# HashUnit2.net
KiCad netlist of a schematic drawn in Altium Designer
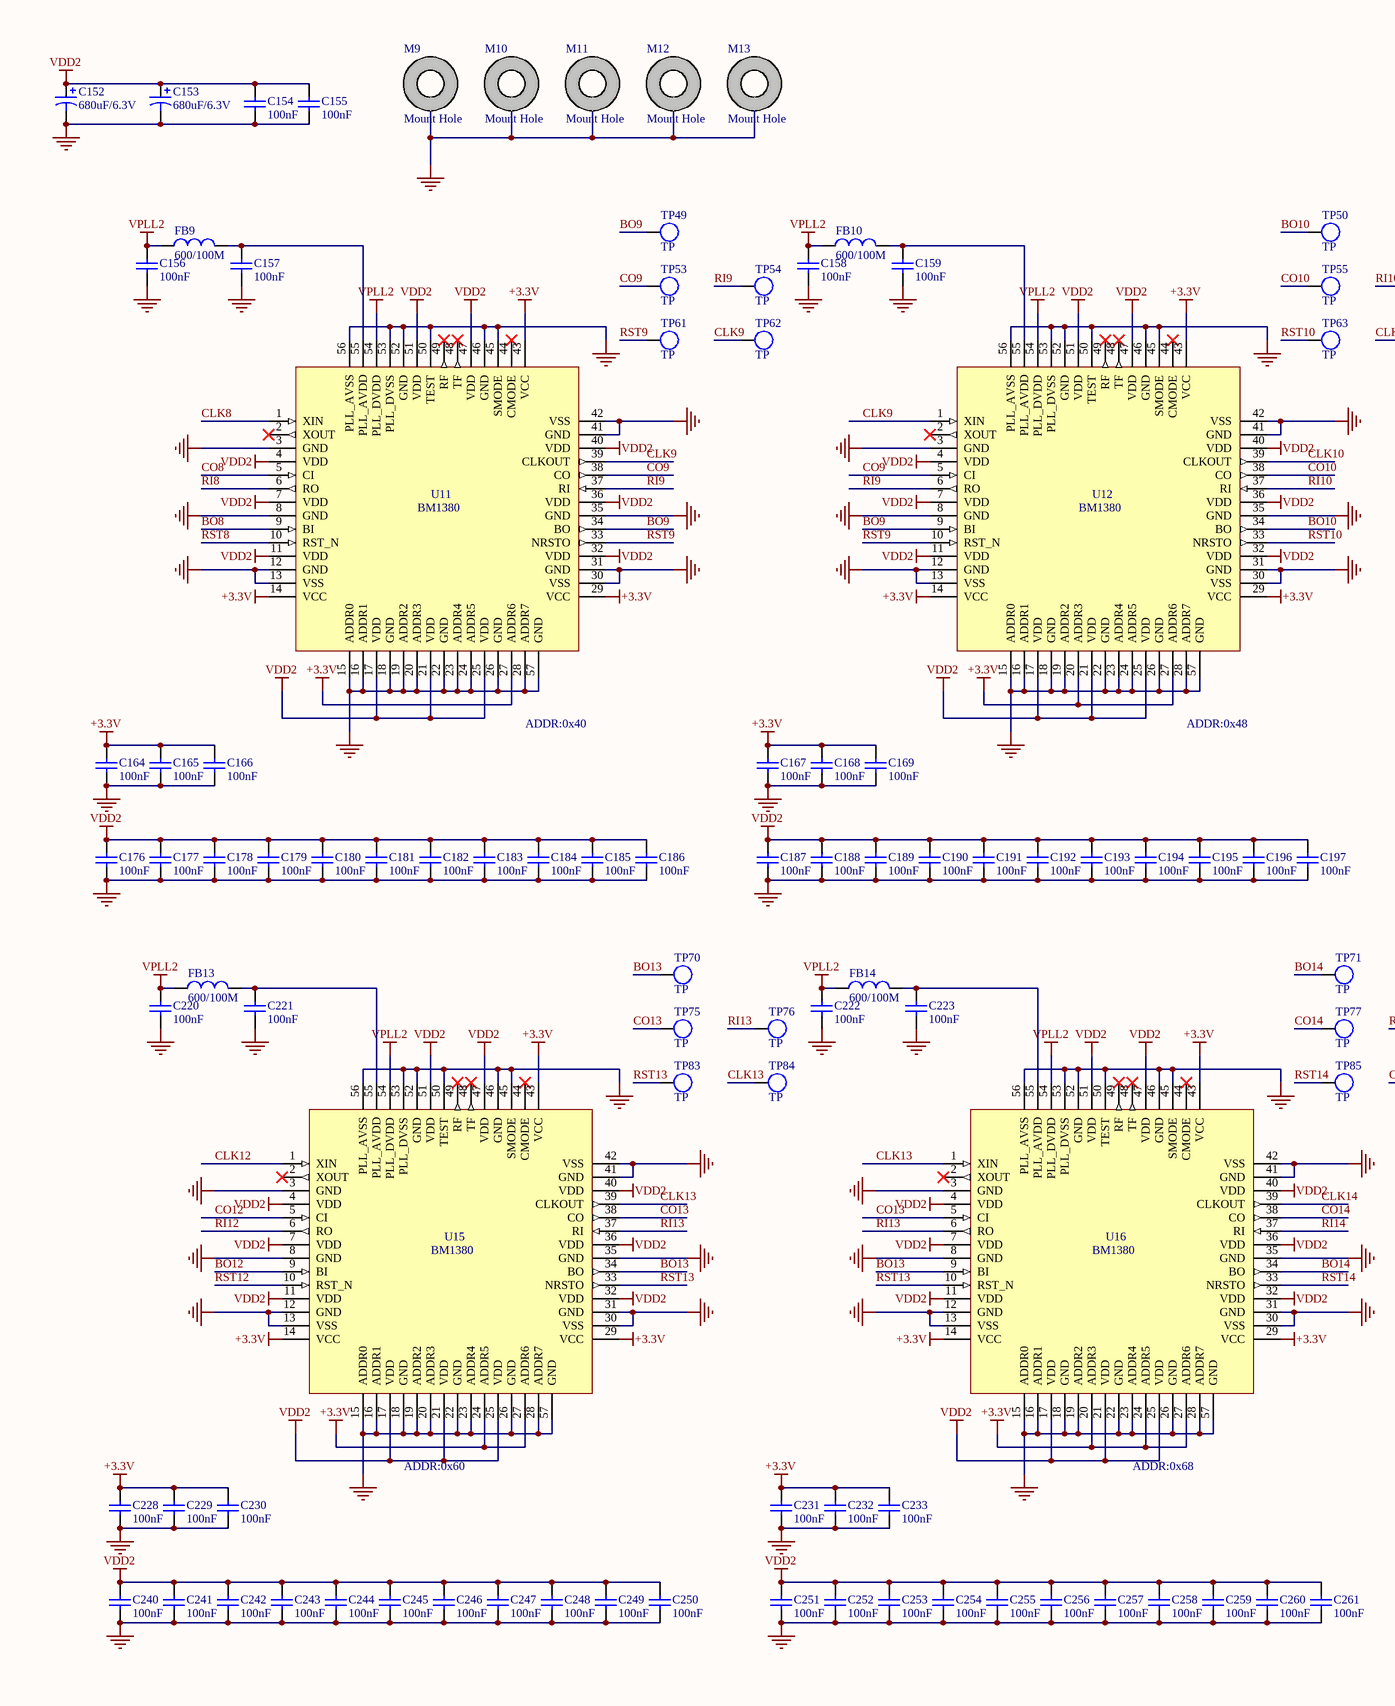
[diagram p0: HashUnit2.SchDoc, left]
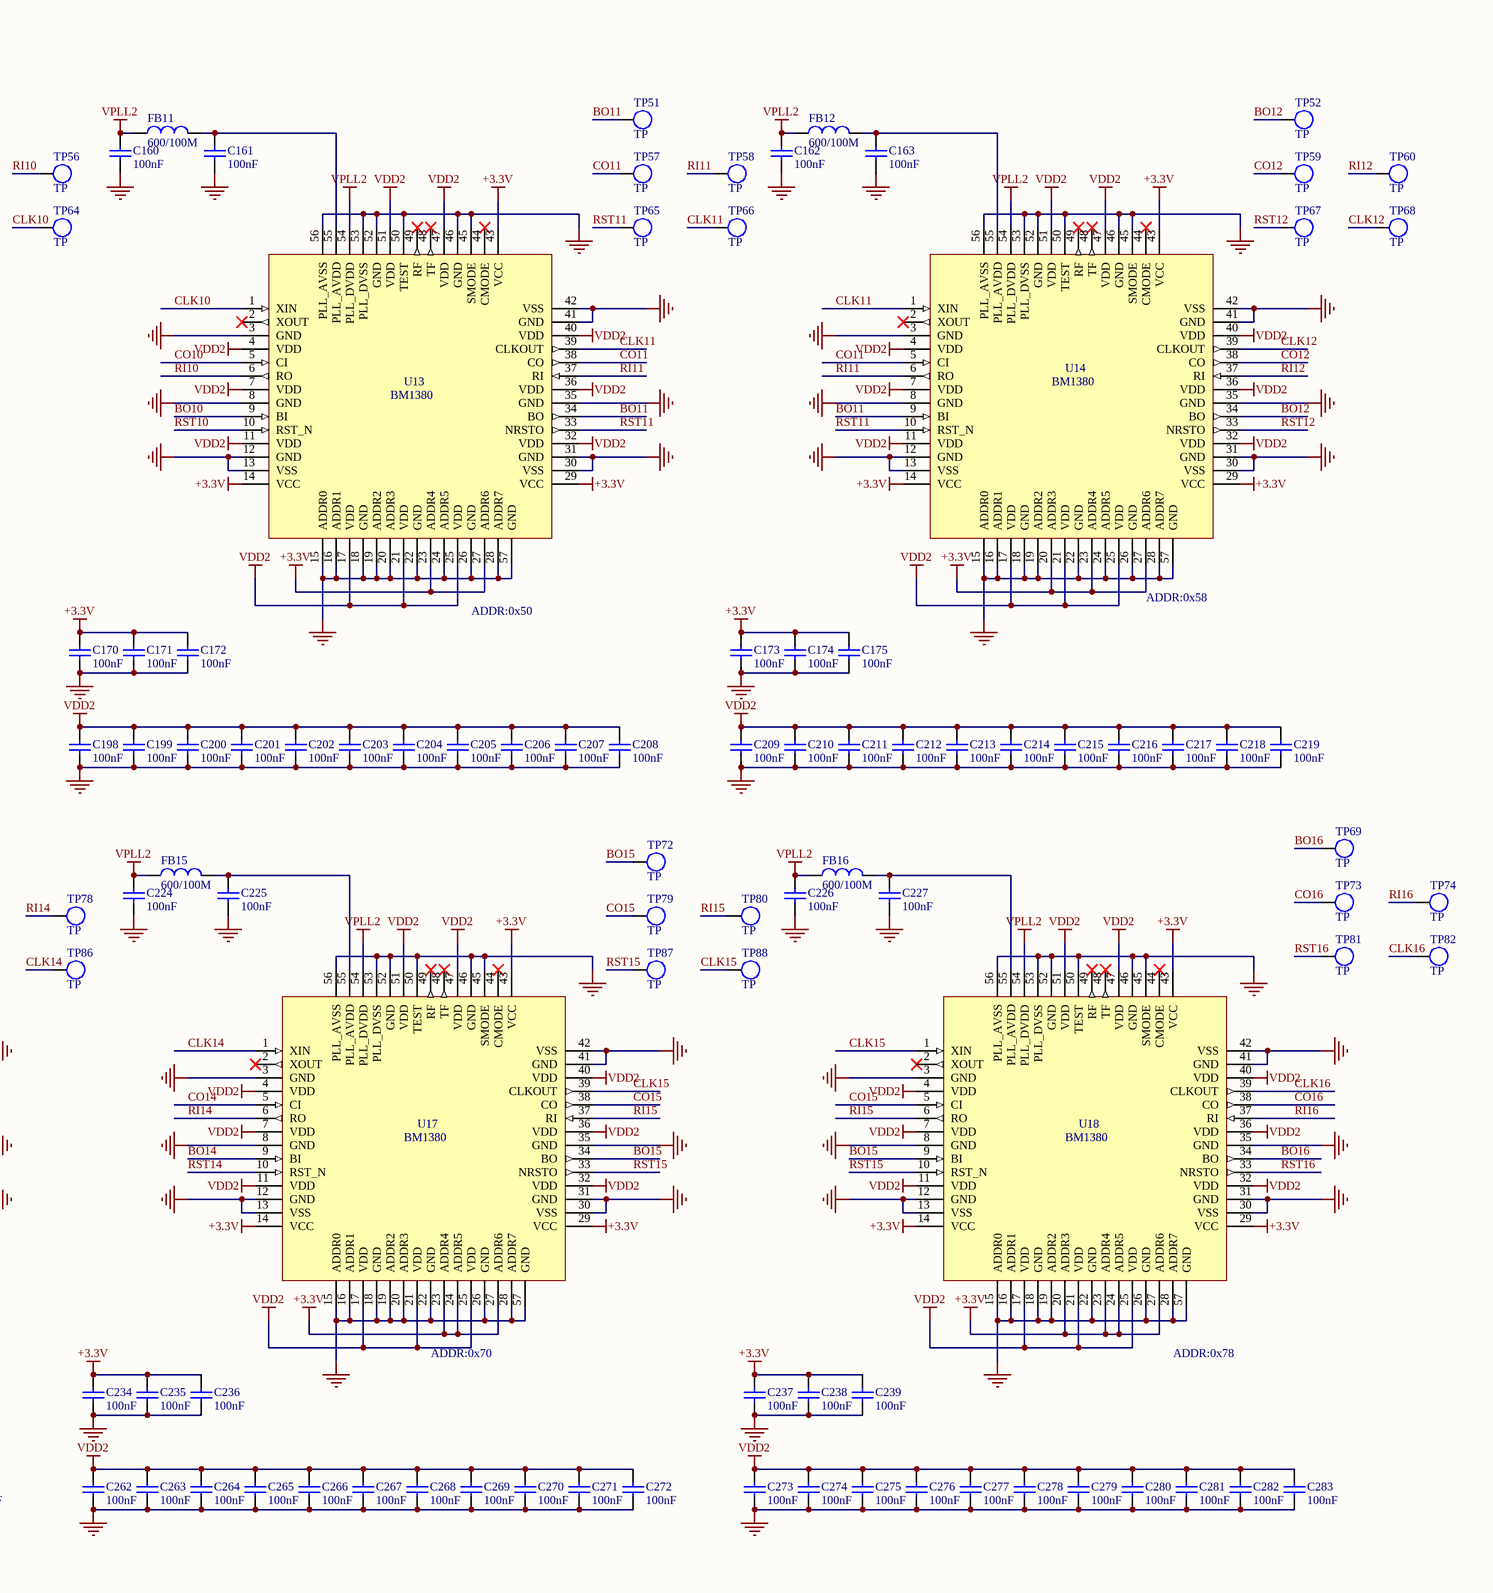
[diagram p1: HashUnit2.SchDoc, right]

(export (version "E")
  (design (tool "Eeschema 10.0.6"))
  (components
    (comp (ref "C152")
      (value "680uF/6.3V")
      (footprint "D")
      (description "Solid Tantalum Chip Capacitor, T492 Series - CWR11 Style Per Mil-PRF-55365/8")
      (fields (field (name "PUBLISHER") "Altium Limited"))
      (libsource (lib "KEMET Chip Capacitor") (part "T492C"))
    )
    (comp (ref "C153")
      (value "680uF/6.3V")
      (footprint "D")
      (description "Solid Tantalum Chip Capacitor, T492 Series - CWR11 Style Per Mil-PRF-55365/8")
      (fields (field (name "PUBLISHER") "Altium Limited"))
      (libsource (lib "KEMET Chip Capacitor") (part "T492C"))
    )
    (comp (ref "C154")
      (value "100nF")
      (footprint "CC0603(1608)")
      (description "Capacitor (Semiconductor SIM Model)")
      (fields (field (name "PUBLISHER") "Altium Limited"))
      (libsource (lib "Miscellaneous Devices") (part "Cap Semi"))
    )
    (comp (ref "C155")
      (value "100nF")
      (footprint "CC0603(1608)")
      (description "Capacitor (Semiconductor SIM Model)")
      (fields (field (name "PUBLISHER") "Altium Limited"))
      (libsource (lib "Miscellaneous Devices") (part "Cap Semi"))
    )
    (comp (ref "C156")
      (value "100nF")
      (footprint "CC0603(1608)")
      (description "Capacitor")
      (fields (field (name "PUBLISHER") "Altium Limited"))
      (libsource (lib "BitMain_Miner_1") (part "Cap"))
    )
    (comp (ref "C157")
      (value "100nF")
      (footprint "CC0603(1608)")
      (description "Capacitor")
      (fields (field (name "PUBLISHER") "Altium Limited"))
      (libsource (lib "BitMain_Miner_1") (part "Cap"))
    )
    (comp (ref "C158")
      (value "100nF")
      (footprint "CC0603(1608)")
      (description "Capacitor")
      (fields (field (name "PUBLISHER") "Altium Limited"))
      (libsource (lib "BitMain_Miner_1") (part "Cap"))
    )
    (comp (ref "C159")
      (value "100nF")
      (footprint "CC0603(1608)")
      (description "Capacitor")
      (fields (field (name "PUBLISHER") "Altium Limited"))
      (libsource (lib "BitMain_Miner_1") (part "Cap"))
    )
    (comp (ref "C160")
      (value "100nF")
      (footprint "CC0603(1608)")
      (description "Capacitor")
      (fields (field (name "PUBLISHER") "Altium Limited"))
      (libsource (lib "BitMain_Miner_1") (part "Cap"))
    )
    (comp (ref "C161")
      (value "100nF")
      (footprint "CC0603(1608)")
      (description "Capacitor")
      (fields (field (name "PUBLISHER") "Altium Limited"))
      (libsource (lib "BitMain_Miner_1") (part "Cap"))
    )
    (comp (ref "C162")
      (value "100nF")
      (footprint "CC0603(1608)")
      (description "Capacitor")
      (fields (field (name "PUBLISHER") "Altium Limited"))
      (libsource (lib "BitMain_Miner_1") (part "Cap"))
    )
    (comp (ref "C163")
      (value "100nF")
      (footprint "CC0603(1608)")
      (description "Capacitor")
      (fields (field (name "PUBLISHER") "Altium Limited"))
      (libsource (lib "BitMain_Miner_1") (part "Cap"))
    )
    (comp (ref "C164")
      (value "100nF")
      (footprint "CC0603(1608)")
      (description "Capacitor")
      (fields (field (name "PUBLISHER") "Altium Limited"))
      (libsource (lib "BitMain_Miner_1") (part "Cap"))
    )
    (comp (ref "C165")
      (value "100nF")
      (footprint "CC0603(1608)")
      (description "Capacitor")
      (fields (field (name "PUBLISHER") "Altium Limited"))
      (libsource (lib "BitMain_Miner_1") (part "Cap"))
    )
    (comp (ref "C166")
      (value "100nF")
      (footprint "CC0603(1608)")
      (description "Capacitor")
      (fields (field (name "PUBLISHER") "Altium Limited"))
      (libsource (lib "BitMain_Miner_1") (part "Cap"))
    )
    (comp (ref "C167")
      (value "100nF")
      (footprint "CC0603(1608)")
      (description "Capacitor")
      (fields (field (name "PUBLISHER") "Altium Limited"))
      (libsource (lib "BitMain_Miner_1") (part "Cap"))
    )
    (comp (ref "C168")
      (value "100nF")
      (footprint "CC0603(1608)")
      (description "Capacitor")
      (fields (field (name "PUBLISHER") "Altium Limited"))
      (libsource (lib "BitMain_Miner_1") (part "Cap"))
    )
    (comp (ref "C169")
      (value "100nF")
      (footprint "CC0603(1608)")
      (description "Capacitor")
      (fields (field (name "PUBLISHER") "Altium Limited"))
      (libsource (lib "BitMain_Miner_1") (part "Cap"))
    )
    (comp (ref "C170")
      (value "100nF")
      (footprint "CC0603(1608)")
      (description "Capacitor")
      (fields (field (name "PUBLISHER") "Altium Limited"))
      (libsource (lib "BitMain_Miner_1") (part "Cap"))
    )
    (comp (ref "C171")
      (value "100nF")
      (footprint "CC0603(1608)")
      (description "Capacitor")
      (fields (field (name "PUBLISHER") "Altium Limited"))
      (libsource (lib "BitMain_Miner_1") (part "Cap"))
    )
    (comp (ref "C172")
      (value "100nF")
      (footprint "CC0603(1608)")
      (description "Capacitor")
      (fields (field (name "PUBLISHER") "Altium Limited"))
      (libsource (lib "BitMain_Miner_1") (part "Cap"))
    )
    (comp (ref "C173")
      (value "100nF")
      (footprint "CC0603(1608)")
      (description "Capacitor")
      (fields (field (name "PUBLISHER") "Altium Limited"))
      (libsource (lib "BitMain_Miner_1") (part "Cap"))
    )
    (comp (ref "C174")
      (value "100nF")
      (footprint "CC0603(1608)")
      (description "Capacitor")
      (fields (field (name "PUBLISHER") "Altium Limited"))
      (libsource (lib "BitMain_Miner_1") (part "Cap"))
    )
    (comp (ref "C175")
      (value "100nF")
      (footprint "CC0603(1608)")
      (description "Capacitor")
      (fields (field (name "PUBLISHER") "Altium Limited"))
      (libsource (lib "BitMain_Miner_1") (part "Cap"))
    )
    (comp (ref "C176")
      (value "100nF")
      (footprint "CC0603(1608)")
      (description "Capacitor")
      (fields (field (name "PUBLISHER") "Altium Limited"))
      (libsource (lib "BitMain_Miner_1") (part "Cap"))
    )
    (comp (ref "C177")
      (value "100nF")
      (footprint "CC0603(1608)")
      (description "Capacitor")
      (fields (field (name "PUBLISHER") "Altium Limited"))
      (libsource (lib "BitMain_Miner_1") (part "Cap"))
    )
    (comp (ref "C178")
      (value "100nF")
      (footprint "CC0603(1608)")
      (description "Capacitor")
      (fields (field (name "PUBLISHER") "Altium Limited"))
      (libsource (lib "BitMain_Miner_1") (part "Cap"))
    )
    (comp (ref "C179")
      (value "100nF")
      (footprint "CC0603(1608)")
      (description "Capacitor")
      (fields (field (name "PUBLISHER") "Altium Limited"))
      (libsource (lib "BitMain_Miner_1") (part "Cap"))
    )
    (comp (ref "C180")
      (value "100nF")
      (footprint "CC0603(1608)")
      (description "Capacitor")
      (fields (field (name "PUBLISHER") "Altium Limited"))
      (libsource (lib "BitMain_Miner_1") (part "Cap"))
    )
    (comp (ref "C181")
      (value "100nF")
      (footprint "CC0603(1608)")
      (description "Capacitor")
      (fields (field (name "PUBLISHER") "Altium Limited"))
      (libsource (lib "BitMain_Miner_1") (part "Cap"))
    )
    (comp (ref "C182")
      (value "100nF")
      (footprint "CC0603(1608)")
      (description "Capacitor")
      (fields (field (name "PUBLISHER") "Altium Limited"))
      (libsource (lib "BitMain_Miner_1") (part "Cap"))
    )
    (comp (ref "C183")
      (value "100nF")
      (footprint "CC0603(1608)")
      (description "Capacitor")
      (fields (field (name "PUBLISHER") "Altium Limited"))
      (libsource (lib "BitMain_Miner_1") (part "Cap"))
    )
    (comp (ref "C184")
      (value "100nF")
      (footprint "CC0603(1608)")
      (description "Capacitor")
      (fields (field (name "PUBLISHER") "Altium Limited"))
      (libsource (lib "BitMain_Miner_1") (part "Cap"))
    )
    (comp (ref "C185")
      (value "100nF")
      (footprint "CC0603(1608)")
      (description "Capacitor")
      (fields (field (name "PUBLISHER") "Altium Limited"))
      (libsource (lib "BitMain_Miner_1") (part "Cap"))
    )
    (comp (ref "C186")
      (value "100nF")
      (footprint "CC0603(1608)")
      (description "Capacitor")
      (fields (field (name "PUBLISHER") "Altium Limited"))
      (libsource (lib "BitMain_Miner_1") (part "Cap"))
    )
    (comp (ref "C187")
      (value "100nF")
      (footprint "CC0603(1608)")
      (description "Capacitor")
      (fields (field (name "PUBLISHER") "Altium Limited"))
      (libsource (lib "BitMain_Miner_1") (part "Cap"))
    )
    (comp (ref "C188")
      (value "100nF")
      (footprint "CC0603(1608)")
      (description "Capacitor")
      (fields (field (name "PUBLISHER") "Altium Limited"))
      (libsource (lib "BitMain_Miner_1") (part "Cap"))
    )
    (comp (ref "C189")
      (value "100nF")
      (footprint "CC0603(1608)")
      (description "Capacitor")
      (fields (field (name "PUBLISHER") "Altium Limited"))
      (libsource (lib "BitMain_Miner_1") (part "Cap"))
    )
    (comp (ref "C190")
      (value "100nF")
      (footprint "CC0603(1608)")
      (description "Capacitor")
      (fields (field (name "PUBLISHER") "Altium Limited"))
      (libsource (lib "BitMain_Miner_1") (part "Cap"))
    )
    (comp (ref "C191")
      (value "100nF")
      (footprint "CC0603(1608)")
      (description "Capacitor")
      (fields (field (name "PUBLISHER") "Altium Limited"))
      (libsource (lib "BitMain_Miner_1") (part "Cap"))
    )
    (comp (ref "C192")
      (value "100nF")
      (footprint "CC0603(1608)")
      (description "Capacitor")
      (fields (field (name "PUBLISHER") "Altium Limited"))
      (libsource (lib "BitMain_Miner_1") (part "Cap"))
    )
    (comp (ref "C193")
      (value "100nF")
      (footprint "CC0603(1608)")
      (description "Capacitor")
      (fields (field (name "PUBLISHER") "Altium Limited"))
      (libsource (lib "BitMain_Miner_1") (part "Cap"))
    )
    (comp (ref "C194")
      (value "100nF")
      (footprint "CC0603(1608)")
      (description "Capacitor")
      (fields (field (name "PUBLISHER") "Altium Limited"))
      (libsource (lib "BitMain_Miner_1") (part "Cap"))
    )
    (comp (ref "C195")
      (value "100nF")
      (footprint "CC0603(1608)")
      (description "Capacitor")
      (fields (field (name "PUBLISHER") "Altium Limited"))
      (libsource (lib "BitMain_Miner_1") (part "Cap"))
    )
    (comp (ref "C196")
      (value "100nF")
      (footprint "CC0603(1608)")
      (description "Capacitor")
      (fields (field (name "PUBLISHER") "Altium Limited"))
      (libsource (lib "BitMain_Miner_1") (part "Cap"))
    )
    (comp (ref "C197")
      (value "100nF")
      (footprint "CC0603(1608)")
      (description "Capacitor")
      (fields (field (name "PUBLISHER") "Altium Limited"))
      (libsource (lib "BitMain_Miner_1") (part "Cap"))
    )
    (comp (ref "C198")
      (value "100nF")
      (footprint "CC0603(1608)")
      (description "Capacitor")
      (fields (field (name "PUBLISHER") "Altium Limited"))
      (libsource (lib "BitMain_Miner_1") (part "Cap"))
    )
    (comp (ref "C199")
      (value "100nF")
      (footprint "CC0603(1608)")
      (description "Capacitor")
      (fields (field (name "PUBLISHER") "Altium Limited"))
      (libsource (lib "BitMain_Miner_1") (part "Cap"))
    )
    (comp (ref "C200")
      (value "100nF")
      (footprint "CC0603(1608)")
      (description "Capacitor")
      (fields (field (name "PUBLISHER") "Altium Limited"))
      (libsource (lib "BitMain_Miner_1") (part "Cap"))
    )
    (comp (ref "C201")
      (value "100nF")
      (footprint "CC0603(1608)")
      (description "Capacitor")
      (fields (field (name "PUBLISHER") "Altium Limited"))
      (libsource (lib "BitMain_Miner_1") (part "Cap"))
    )
    (comp (ref "C202")
      (value "100nF")
      (footprint "CC0603(1608)")
      (description "Capacitor")
      (fields (field (name "PUBLISHER") "Altium Limited"))
      (libsource (lib "BitMain_Miner_1") (part "Cap"))
    )
    (comp (ref "C203")
      (value "100nF")
      (footprint "CC0603(1608)")
      (description "Capacitor")
      (fields (field (name "PUBLISHER") "Altium Limited"))
      (libsource (lib "BitMain_Miner_1") (part "Cap"))
    )
    (comp (ref "C204")
      (value "100nF")
      (footprint "CC0603(1608)")
      (description "Capacitor")
      (fields (field (name "PUBLISHER") "Altium Limited"))
      (libsource (lib "BitMain_Miner_1") (part "Cap"))
    )
    (comp (ref "C205")
      (value "100nF")
      (footprint "CC0603(1608)")
      (description "Capacitor")
      (fields (field (name "PUBLISHER") "Altium Limited"))
      (libsource (lib "BitMain_Miner_1") (part "Cap"))
    )
    (comp (ref "C206")
      (value "100nF")
      (footprint "CC0603(1608)")
      (description "Capacitor")
      (fields (field (name "PUBLISHER") "Altium Limited"))
      (libsource (lib "BitMain_Miner_1") (part "Cap"))
    )
    (comp (ref "C207")
      (value "100nF")
      (footprint "CC0603(1608)")
      (description "Capacitor")
      (fields (field (name "PUBLISHER") "Altium Limited"))
      (libsource (lib "BitMain_Miner_1") (part "Cap"))
    )
    (comp (ref "C208")
      (value "100nF")
      (footprint "CC0603(1608)")
      (description "Capacitor")
      (fields (field (name "PUBLISHER") "Altium Limited"))
      (libsource (lib "BitMain_Miner_1") (part "Cap"))
    )
    (comp (ref "C209")
      (value "100nF")
      (footprint "CC0603(1608)")
      (description "Capacitor")
      (fields (field (name "PUBLISHER") "Altium Limited"))
      (libsource (lib "BitMain_Miner_1") (part "Cap"))
    )
    (comp (ref "C210")
      (value "100nF")
      (footprint "CC0603(1608)")
      (description "Capacitor")
      (fields (field (name "PUBLISHER") "Altium Limited"))
      (libsource (lib "BitMain_Miner_1") (part "Cap"))
    )
    (comp (ref "C211")
      (value "100nF")
      (footprint "CC0603(1608)")
      (description "Capacitor")
      (fields (field (name "PUBLISHER") "Altium Limited"))
      (libsource (lib "BitMain_Miner_1") (part "Cap"))
    )
    (comp (ref "C212")
      (value "100nF")
      (footprint "CC0603(1608)")
      (description "Capacitor")
      (fields (field (name "PUBLISHER") "Altium Limited"))
      (libsource (lib "BitMain_Miner_1") (part "Cap"))
    )
    (comp (ref "C213")
      (value "100nF")
      (footprint "CC0603(1608)")
      (description "Capacitor")
      (fields (field (name "PUBLISHER") "Altium Limited"))
      (libsource (lib "BitMain_Miner_1") (part "Cap"))
    )
    (comp (ref "C214")
      (value "100nF")
      (footprint "CC0603(1608)")
      (description "Capacitor")
      (fields (field (name "PUBLISHER") "Altium Limited"))
      (libsource (lib "BitMain_Miner_1") (part "Cap"))
    )
    (comp (ref "C215")
      (value "100nF")
      (footprint "CC0603(1608)")
      (description "Capacitor")
      (fields (field (name "PUBLISHER") "Altium Limited"))
      (libsource (lib "BitMain_Miner_1") (part "Cap"))
    )
    (comp (ref "C216")
      (value "100nF")
      (footprint "CC0603(1608)")
      (description "Capacitor")
      (fields (field (name "PUBLISHER") "Altium Limited"))
      (libsource (lib "BitMain_Miner_1") (part "Cap"))
    )
    (comp (ref "C217")
      (value "100nF")
      (footprint "CC0603(1608)")
      (description "Capacitor")
      (fields (field (name "PUBLISHER") "Altium Limited"))
      (libsource (lib "BitMain_Miner_1") (part "Cap"))
    )
    (comp (ref "C218")
      (value "100nF")
      (footprint "CC0603(1608)")
      (description "Capacitor")
      (fields (field (name "PUBLISHER") "Altium Limited"))
      (libsource (lib "BitMain_Miner_1") (part "Cap"))
    )
    (comp (ref "C219")
      (value "100nF")
      (footprint "CC0603(1608)")
      (description "Capacitor")
      (fields (field (name "PUBLISHER") "Altium Limited"))
      (libsource (lib "BitMain_Miner_1") (part "Cap"))
    )
    (comp (ref "C220")
      (value "100nF")
      (footprint "CC0603(1608)")
      (description "Capacitor")
      (fields (field (name "PUBLISHER") "Altium Limited"))
      (libsource (lib "BitMain_Miner_1") (part "Cap"))
    )
    (comp (ref "C221")
      (value "100nF")
      (footprint "CC0603(1608)")
      (description "Capacitor")
      (fields (field (name "PUBLISHER") "Altium Limited"))
      (libsource (lib "BitMain_Miner_1") (part "Cap"))
    )
    (comp (ref "C222")
      (value "100nF")
      (footprint "CC0603(1608)")
      (description "Capacitor")
      (fields (field (name "PUBLISHER") "Altium Limited"))
      (libsource (lib "BitMain_Miner_1") (part "Cap"))
    )
    (comp (ref "C223")
      (value "100nF")
      (footprint "CC0603(1608)")
      (description "Capacitor")
      (fields (field (name "PUBLISHER") "Altium Limited"))
      (libsource (lib "BitMain_Miner_1") (part "Cap"))
    )
    (comp (ref "C224")
      (value "100nF")
      (footprint "CC0603(1608)")
      (description "Capacitor")
      (fields (field (name "PUBLISHER") "Altium Limited"))
      (libsource (lib "BitMain_Miner_1") (part "Cap"))
    )
    (comp (ref "C225")
      (value "100nF")
      (footprint "CC0603(1608)")
      (description "Capacitor")
      (fields (field (name "PUBLISHER") "Altium Limited"))
      (libsource (lib "BitMain_Miner_1") (part "Cap"))
    )
    (comp (ref "C226")
      (value "100nF")
      (footprint "CC0603(1608)")
      (description "Capacitor")
      (fields (field (name "PUBLISHER") "Altium Limited"))
      (libsource (lib "BitMain_Miner_1") (part "Cap"))
    )
    (comp (ref "C227")
      (value "100nF")
      (footprint "CC0603(1608)")
      (description "Capacitor")
      (fields (field (name "PUBLISHER") "Altium Limited"))
      (libsource (lib "BitMain_Miner_1") (part "Cap"))
    )
    (comp (ref "C228")
      (value "100nF")
      (footprint "CC0603(1608)")
      (description "Capacitor")
      (fields (field (name "PUBLISHER") "Altium Limited"))
      (libsource (lib "BitMain_Miner_1") (part "Cap"))
    )
    (comp (ref "C229")
      (value "100nF")
      (footprint "CC0603(1608)")
      (description "Capacitor")
      (fields (field (name "PUBLISHER") "Altium Limited"))
      (libsource (lib "BitMain_Miner_1") (part "Cap"))
    )
    (comp (ref "C230")
      (value "100nF")
      (footprint "CC0603(1608)")
      (description "Capacitor")
      (fields (field (name "PUBLISHER") "Altium Limited"))
      (libsource (lib "BitMain_Miner_1") (part "Cap"))
    )
    (comp (ref "C231")
      (value "100nF")
      (footprint "CC0603(1608)")
      (description "Capacitor")
      (fields (field (name "PUBLISHER") "Altium Limited"))
      (libsource (lib "BitMain_Miner_1") (part "Cap"))
    )
    (comp (ref "C232")
      (value "100nF")
      (footprint "CC0603(1608)")
      (description "Capacitor")
      (fields (field (name "PUBLISHER") "Altium Limited"))
      (libsource (lib "BitMain_Miner_1") (part "Cap"))
    )
    (comp (ref "C233")
      (value "100nF")
      (footprint "CC0603(1608)")
      (description "Capacitor")
      (fields (field (name "PUBLISHER") "Altium Limited"))
      (libsource (lib "BitMain_Miner_1") (part "Cap"))
    )
    (comp (ref "C234")
      (value "100nF")
      (footprint "CC0603(1608)")
      (description "Capacitor")
      (fields (field (name "PUBLISHER") "Altium Limited"))
      (libsource (lib "BitMain_Miner_1") (part "Cap"))
    )
    (comp (ref "C235")
      (value "100nF")
      (footprint "CC0603(1608)")
      (description "Capacitor")
      (fields (field (name "PUBLISHER") "Altium Limited"))
      (libsource (lib "BitMain_Miner_1") (part "Cap"))
    )
    (comp (ref "C236")
      (value "100nF")
      (footprint "CC0603(1608)")
      (description "Capacitor")
      (fields (field (name "PUBLISHER") "Altium Limited"))
      (libsource (lib "BitMain_Miner_1") (part "Cap"))
    )
    (comp (ref "C237")
      (value "100nF")
      (footprint "CC0603(1608)")
      (description "Capacitor")
      (fields (field (name "PUBLISHER") "Altium Limited"))
      (libsource (lib "BitMain_Miner_1") (part "Cap"))
    )
    (comp (ref "C238")
      (value "100nF")
      (footprint "CC0603(1608)")
      (description "Capacitor")
      (fields (field (name "PUBLISHER") "Altium Limited"))
      (libsource (lib "BitMain_Miner_1") (part "Cap"))
    )
    (comp (ref "C239")
      (value "100nF")
      (footprint "CC0603(1608)")
      (description "Capacitor")
      (fields (field (name "PUBLISHER") "Altium Limited"))
      (libsource (lib "BitMain_Miner_1") (part "Cap"))
    )
    (comp (ref "C240")
      (value "100nF")
      (footprint "CC0603(1608)")
      (description "Capacitor")
      (fields (field (name "PUBLISHER") "Altium Limited"))
      (libsource (lib "BitMain_Miner_1") (part "Cap"))
    )
    (comp (ref "C241")
      (value "100nF")
      (footprint "CC0603(1608)")
      (description "Capacitor")
      (fields (field (name "PUBLISHER") "Altium Limited"))
      (libsource (lib "BitMain_Miner_1") (part "Cap"))
    )
    (comp (ref "C242")
      (value "100nF")
      (footprint "CC0603(1608)")
      (description "Capacitor")
      (fields (field (name "PUBLISHER") "Altium Limited"))
      (libsource (lib "BitMain_Miner_1") (part "Cap"))
    )
    (comp (ref "C243")
      (value "100nF")
      (footprint "CC0603(1608)")
      (description "Capacitor")
      (fields (field (name "PUBLISHER") "Altium Limited"))
      (libsource (lib "BitMain_Miner_1") (part "Cap"))
    )
    (comp (ref "C244")
      (value "100nF")
      (footprint "CC0603(1608)")
      (description "Capacitor")
      (fields (field (name "PUBLISHER") "Altium Limited"))
      (libsource (lib "BitMain_Miner_1") (part "Cap"))
    )
    (comp (ref "C245")
      (value "100nF")
      (footprint "CC0603(1608)")
      (description "Capacitor")
      (fields (field (name "PUBLISHER") "Altium Limited"))
      (libsource (lib "BitMain_Miner_1") (part "Cap"))
    )
    (comp (ref "C246")
      (value "100nF")
      (footprint "CC0603(1608)")
      (description "Capacitor")
      (fields (field (name "PUBLISHER") "Altium Limited"))
      (libsource (lib "BitMain_Miner_1") (part "Cap"))
    )
    (comp (ref "C247")
      (value "100nF")
      (footprint "CC0603(1608)")
      (description "Capacitor")
      (fields (field (name "PUBLISHER") "Altium Limited"))
      (libsource (lib "BitMain_Miner_1") (part "Cap"))
    )
    (comp (ref "C248")
      (value "100nF")
      (footprint "CC0603(1608)")
      (description "Capacitor")
      (fields (field (name "PUBLISHER") "Altium Limited"))
      (libsource (lib "BitMain_Miner_1") (part "Cap"))
    )
    (comp (ref "C249")
      (value "100nF")
      (footprint "CC0603(1608)")
      (description "Capacitor")
      (fields (field (name "PUBLISHER") "Altium Limited"))
      (libsource (lib "BitMain_Miner_1") (part "Cap"))
    )
    (comp (ref "C250")
      (value "100nF")
      (footprint "CC0603(1608)")
      (description "Capacitor")
      (fields (field (name "PUBLISHER") "Altium Limited"))
      (libsource (lib "BitMain_Miner_1") (part "Cap"))
    )
    (comp (ref "C251")
      (value "100nF")
      (footprint "CC0603(1608)")
      (description "Capacitor")
      (fields (field (name "PUBLISHER") "Altium Limited"))
      (libsource (lib "BitMain_Miner_1") (part "Cap"))
    )
    (comp (ref "C252")
      (value "100nF")
      (footprint "CC0603(1608)")
      (description "Capacitor")
      (fields (field (name "PUBLISHER") "Altium Limited"))
      (libsource (lib "BitMain_Miner_1") (part "Cap"))
    )
    (comp (ref "C253")
      (value "100nF")
      (footprint "CC0603(1608)")
      (description "Capacitor")
      (fields (field (name "PUBLISHER") "Altium Limited"))
      (libsource (lib "BitMain_Miner_1") (part "Cap"))
    )
    (comp (ref "C254")
      (value "100nF")
      (footprint "CC0603(1608)")
      (description "Capacitor")
      (fields (field (name "PUBLISHER") "Altium Limited"))
      (libsource (lib "BitMain_Miner_1") (part "Cap"))
    )
    (comp (ref "C255")
      (value "100nF")
      (footprint "CC0603(1608)")
      (description "Capacitor")
      (fields (field (name "PUBLISHER") "Altium Limited"))
      (libsource (lib "BitMain_Miner_1") (part "Cap"))
    )
    (comp (ref "C256")
      (value "100nF")
      (footprint "CC0603(1608)")
      (description "Capacitor")
      (fields (field (name "PUBLISHER") "Altium Limited"))
      (libsource (lib "BitMain_Miner_1") (part "Cap"))
    )
    (comp (ref "C257")
      (value "100nF")
      (footprint "CC0603(1608)")
      (description "Capacitor")
      (fields (field (name "PUBLISHER") "Altium Limited"))
      (libsource (lib "BitMain_Miner_1") (part "Cap"))
    )
    (comp (ref "C258")
      (value "100nF")
      (footprint "CC0603(1608)")
      (description "Capacitor")
      (fields (field (name "PUBLISHER") "Altium Limited"))
      (libsource (lib "BitMain_Miner_1") (part "Cap"))
    )
    (comp (ref "C259")
      (value "100nF")
      (footprint "CC0603(1608)")
      (description "Capacitor")
      (fields (field (name "PUBLISHER") "Altium Limited"))
      (libsource (lib "BitMain_Miner_1") (part "Cap"))
    )
    (comp (ref "C260")
      (value "100nF")
      (footprint "CC0603(1608)")
      (description "Capacitor")
      (fields (field (name "PUBLISHER") "Altium Limited"))
      (libsource (lib "BitMain_Miner_1") (part "Cap"))
    )
    (comp (ref "C261")
      (value "100nF")
      (footprint "CC0603(1608)")
      (description "Capacitor")
      (fields (field (name "PUBLISHER") "Altium Limited"))
      (libsource (lib "BitMain_Miner_1") (part "Cap"))
    )
    (comp (ref "C262")
      (value "100nF")
      (footprint "CC0603(1608)")
      (description "Capacitor")
      (fields (field (name "PUBLISHER") "Altium Limited"))
      (libsource (lib "BitMain_Miner_1") (part "Cap"))
    )
    (comp (ref "C263")
      (value "100nF")
      (footprint "CC0603(1608)")
      (description "Capacitor")
      (fields (field (name "PUBLISHER") "Altium Limited"))
      (libsource (lib "BitMain_Miner_1") (part "Cap"))
    )
    (comp (ref "C264")
      (value "100nF")
      (footprint "CC0603(1608)")
      (description "Capacitor")
      (fields (field (name "PUBLISHER") "Altium Limited"))
      (libsource (lib "BitMain_Miner_1") (part "Cap"))
    )
    (comp (ref "C265")
      (value "100nF")
      (footprint "CC0603(1608)")
      (description "Capacitor")
      (fields (field (name "PUBLISHER") "Altium Limited"))
      (libsource (lib "BitMain_Miner_1") (part "Cap"))
    )
    (comp (ref "C266")
      (value "100nF")
      (footprint "CC0603(1608)")
      (description "Capacitor")
      (fields (field (name "PUBLISHER") "Altium Limited"))
      (libsource (lib "BitMain_Miner_1") (part "Cap"))
    )
    (comp (ref "C267")
      (value "100nF")
      (footprint "CC0603(1608)")
      (description "Capacitor")
      (fields (field (name "PUBLISHER") "Altium Limited"))
      (libsource (lib "BitMain_Miner_1") (part "Cap"))
    )
    (comp (ref "C268")
      (value "100nF")
      (footprint "CC0603(1608)")
      (description "Capacitor")
      (fields (field (name "PUBLISHER") "Altium Limited"))
      (libsource (lib "BitMain_Miner_1") (part "Cap"))
    )
    (comp (ref "C269")
      (value "100nF")
      (footprint "CC0603(1608)")
      (description "Capacitor")
      (fields (field (name "PUBLISHER") "Altium Limited"))
      (libsource (lib "BitMain_Miner_1") (part "Cap"))
    )
    (comp (ref "C270")
      (value "100nF")
      (footprint "CC0603(1608)")
      (description "Capacitor")
      (fields (field (name "PUBLISHER") "Altium Limited"))
      (libsource (lib "BitMain_Miner_1") (part "Cap"))
    )
    (comp (ref "C271")
      (value "100nF")
      (footprint "CC0603(1608)")
      (description "Capacitor")
      (fields (field (name "PUBLISHER") "Altium Limited"))
      (libsource (lib "BitMain_Miner_1") (part "Cap"))
    )
    (comp (ref "C272")
      (value "100nF")
      (footprint "CC0603(1608)")
      (description "Capacitor")
      (fields (field (name "PUBLISHER") "Altium Limited"))
      (libsource (lib "BitMain_Miner_1") (part "Cap"))
    )
    (comp (ref "C273")
      (value "100nF")
      (footprint "CC0603(1608)")
      (description "Capacitor")
      (fields (field (name "PUBLISHER") "Altium Limited"))
      (libsource (lib "BitMain_Miner_1") (part "Cap"))
    )
    (comp (ref "C274")
      (value "100nF")
      (footprint "CC0603(1608)")
      (description "Capacitor")
      (fields (field (name "PUBLISHER") "Altium Limited"))
      (libsource (lib "BitMain_Miner_1") (part "Cap"))
    )
    (comp (ref "C275")
      (value "100nF")
      (footprint "CC0603(1608)")
      (description "Capacitor")
      (fields (field (name "PUBLISHER") "Altium Limited"))
      (libsource (lib "BitMain_Miner_1") (part "Cap"))
    )
    (comp (ref "C276")
      (value "100nF")
      (footprint "CC0603(1608)")
      (description "Capacitor")
      (fields (field (name "PUBLISHER") "Altium Limited"))
      (libsource (lib "BitMain_Miner_1") (part "Cap"))
    )
    (comp (ref "C277")
      (value "100nF")
      (footprint "CC0603(1608)")
      (description "Capacitor")
      (fields (field (name "PUBLISHER") "Altium Limited"))
      (libsource (lib "BitMain_Miner_1") (part "Cap"))
    )
    (comp (ref "C278")
      (value "100nF")
      (footprint "CC0603(1608)")
      (description "Capacitor")
      (fields (field (name "PUBLISHER") "Altium Limited"))
      (libsource (lib "BitMain_Miner_1") (part "Cap"))
    )
    (comp (ref "C279")
      (value "100nF")
      (footprint "CC0603(1608)")
      (description "Capacitor")
      (fields (field (name "PUBLISHER") "Altium Limited"))
      (libsource (lib "BitMain_Miner_1") (part "Cap"))
    )
    (comp (ref "C280")
      (value "100nF")
      (footprint "CC0603(1608)")
      (description "Capacitor")
      (fields (field (name "PUBLISHER") "Altium Limited"))
      (libsource (lib "BitMain_Miner_1") (part "Cap"))
    )
    (comp (ref "C281")
      (value "100nF")
      (footprint "CC0603(1608)")
      (description "Capacitor")
      (fields (field (name "PUBLISHER") "Altium Limited"))
      (libsource (lib "BitMain_Miner_1") (part "Cap"))
    )
    (comp (ref "C282")
      (value "100nF")
      (footprint "CC0603(1608)")
      (description "Capacitor")
      (fields (field (name "PUBLISHER") "Altium Limited"))
      (libsource (lib "BitMain_Miner_1") (part "Cap"))
    )
    (comp (ref "C283")
      (value "100nF")
      (footprint "CC0603(1608)")
      (description "Capacitor")
      (fields (field (name "PUBLISHER") "Altium Limited"))
      (libsource (lib "BitMain_Miner_1") (part "Cap"))
    )
    (comp (ref "FB9")
      (value "600/100M")
      (footprint "FB0603(1608)")
      (description "Inductor")
      (fields (field (name "PUBLISHER") "Altium Limited"))
      (libsource (lib "BitMain_Miner_1") (part "FB"))
    )
    (comp (ref "FB10")
      (value "600/100M")
      (footprint "FB0603(1608)")
      (description "Inductor")
      (fields (field (name "PUBLISHER") "Altium Limited"))
      (libsource (lib "BitMain_Miner_1") (part "FB"))
    )
    (comp (ref "FB11")
      (value "600/100M")
      (footprint "FB0603(1608)")
      (description "Inductor")
      (fields (field (name "PUBLISHER") "Altium Limited"))
      (libsource (lib "BitMain_Miner_1") (part "FB"))
    )
    (comp (ref "FB12")
      (value "600/100M")
      (footprint "FB0603(1608)")
      (description "Inductor")
      (fields (field (name "PUBLISHER") "Altium Limited"))
      (libsource (lib "BitMain_Miner_1") (part "FB"))
    )
    (comp (ref "FB13")
      (value "600/100M")
      (footprint "FB0603(1608)")
      (description "Inductor")
      (fields (field (name "PUBLISHER") "Altium Limited"))
      (libsource (lib "BitMain_Miner_1") (part "FB"))
    )
    (comp (ref "FB14")
      (value "600/100M")
      (footprint "FB0603(1608)")
      (description "Inductor")
      (fields (field (name "PUBLISHER") "Altium Limited"))
      (libsource (lib "BitMain_Miner_1") (part "FB"))
    )
    (comp (ref "FB15")
      (value "600/100M")
      (footprint "FB0603(1608)")
      (description "Inductor")
      (fields (field (name "PUBLISHER") "Altium Limited"))
      (libsource (lib "BitMain_Miner_1") (part "FB"))
    )
    (comp (ref "FB16")
      (value "600/100M")
      (footprint "FB0603(1608)")
      (description "Inductor")
      (fields (field (name "PUBLISHER") "Altium Limited"))
      (libsource (lib "BitMain_Miner_1") (part "FB"))
    )
    (comp (ref "M9") (value "Mount Hole") (footprint "MHOLE2") (libsource (lib "S6_2") (part "M_Hole")))
    (comp (ref "M10") (value "Mount Hole") (footprint "MHOLE2") (libsource (lib "S6_2") (part "M_Hole")))
    (comp (ref "M11") (value "Mount Hole") (footprint "MHOLE2") (libsource (lib "S6_2") (part "M_Hole")))
    (comp (ref "M12") (value "Mount Hole") (footprint "MHOLE2") (libsource (lib "S6_2") (part "M_Hole")))
    (comp (ref "M13") (value "Mount Hole") (footprint "MHOLE2") (libsource (lib "S6_2") (part "M_Hole")))
    (comp (ref "TP49")
      (value "TP")
      (footprint "TP_SMD")
      (description "Test Point")
      (libsource (lib "BitMain_Miner_1") (part "TP"))
    )
    (comp (ref "TP50")
      (value "TP")
      (footprint "TP_SMD")
      (description "Test Point")
      (libsource (lib "BitMain_Miner_1") (part "TP"))
    )
    (comp (ref "TP51")
      (value "TP")
      (footprint "TP_SMD")
      (description "Test Point")
      (libsource (lib "BitMain_Miner_1") (part "TP"))
    )
    (comp (ref "TP52")
      (value "TP")
      (footprint "TP_SMD")
      (description "Test Point")
      (libsource (lib "BitMain_Miner_1") (part "TP"))
    )
    (comp (ref "TP53")
      (value "TP")
      (footprint "TP_SMD")
      (description "Test Point")
      (libsource (lib "BitMain_Miner_1") (part "TP"))
    )
    (comp (ref "TP54")
      (value "TP")
      (footprint "TP_SMD")
      (description "Test Point")
      (libsource (lib "BitMain_Miner_1") (part "TP"))
    )
    (comp (ref "TP55")
      (value "TP")
      (footprint "TP_SMD")
      (description "Test Point")
      (libsource (lib "BitMain_Miner_1") (part "TP"))
    )
    (comp (ref "TP56")
      (value "TP")
      (footprint "TP_SMD")
      (description "Test Point")
      (libsource (lib "BitMain_Miner_1") (part "TP"))
    )
    (comp (ref "TP57")
      (value "TP")
      (footprint "TP_SMD")
      (description "Test Point")
      (libsource (lib "BitMain_Miner_1") (part "TP"))
    )
    (comp (ref "TP58")
      (value "TP")
      (footprint "TP_SMD")
      (description "Test Point")
      (libsource (lib "BitMain_Miner_1") (part "TP"))
    )
    (comp (ref "TP59")
      (value "TP")
      (footprint "TP_SMD")
      (description "Test Point")
      (libsource (lib "BitMain_Miner_1") (part "TP"))
    )
    (comp (ref "TP60")
      (value "TP")
      (footprint "TP_SMD")
      (description "Test Point")
      (libsource (lib "BitMain_Miner_1") (part "TP"))
    )
    (comp (ref "TP61")
      (value "TP")
      (footprint "TP_SMD")
      (description "Test Point")
      (libsource (lib "BitMain_Miner_1") (part "TP"))
    )
    (comp (ref "TP62")
      (value "TP")
      (footprint "TP_SMD")
      (description "Test Point")
      (libsource (lib "BitMain_Miner_1") (part "TP"))
    )
    (comp (ref "TP63")
      (value "TP")
      (footprint "TP_SMD")
      (description "Test Point")
      (libsource (lib "BitMain_Miner_1") (part "TP"))
    )
    (comp (ref "TP64")
      (value "TP")
      (footprint "TP_SMD")
      (description "Test Point")
      (libsource (lib "BitMain_Miner_1") (part "TP"))
    )
    (comp (ref "TP65")
      (value "TP")
      (footprint "TP_SMD")
      (description "Test Point")
      (libsource (lib "BitMain_Miner_1") (part "TP"))
    )
    (comp (ref "TP66")
      (value "TP")
      (footprint "TP_SMD")
      (description "Test Point")
      (libsource (lib "BitMain_Miner_1") (part "TP"))
    )
    (comp (ref "TP67")
      (value "TP")
      (footprint "TP_SMD")
      (description "Test Point")
      (libsource (lib "BitMain_Miner_1") (part "TP"))
    )
    (comp (ref "TP68")
      (value "TP")
      (footprint "TP_SMD")
      (description "Test Point")
      (libsource (lib "BitMain_Miner_1") (part "TP"))
    )
    (comp (ref "TP69")
      (value "TP")
      (footprint "TP_SMD")
      (description "Test Point")
      (libsource (lib "BitMain_Miner_1") (part "TP"))
    )
    (comp (ref "TP70")
      (value "TP")
      (footprint "TP_SMD")
      (description "Test Point")
      (libsource (lib "BitMain_Miner_1") (part "TP"))
    )
    (comp (ref "TP71")
      (value "TP")
      (footprint "TP_SMD")
      (description "Test Point")
      (libsource (lib "BitMain_Miner_1") (part "TP"))
    )
    (comp (ref "TP72")
      (value "TP")
      (footprint "TP_SMD")
      (description "Test Point")
      (libsource (lib "BitMain_Miner_1") (part "TP"))
    )
    (comp (ref "TP73")
      (value "TP")
      (footprint "TP_SMD")
      (description "Test Point")
      (libsource (lib "BitMain_Miner_1") (part "TP"))
    )
    (comp (ref "TP74")
      (value "TP")
      (footprint "TP_SMD")
      (description "Test Point")
      (libsource (lib "BitMain_Miner_1") (part "TP"))
    )
    (comp (ref "TP75")
      (value "TP")
      (footprint "TP_SMD")
      (description "Test Point")
      (libsource (lib "BitMain_Miner_1") (part "TP"))
    )
    (comp (ref "TP76")
      (value "TP")
      (footprint "TP_SMD")
      (description "Test Point")
      (libsource (lib "BitMain_Miner_1") (part "TP"))
    )
    (comp (ref "TP77")
      (value "TP")
      (footprint "TP_SMD")
      (description "Test Point")
      (libsource (lib "BitMain_Miner_1") (part "TP"))
    )
    (comp (ref "TP78")
      (value "TP")
      (footprint "TP_SMD")
      (description "Test Point")
      (libsource (lib "BitMain_Miner_1") (part "TP"))
    )
    (comp (ref "TP79")
      (value "TP")
      (footprint "TP_SMD")
      (description "Test Point")
      (libsource (lib "BitMain_Miner_1") (part "TP"))
    )
    (comp (ref "TP80")
      (value "TP")
      (footprint "TP_SMD")
      (description "Test Point")
      (libsource (lib "BitMain_Miner_1") (part "TP"))
    )
    (comp (ref "TP81")
      (value "TP")
      (footprint "TP_SMD")
      (description "Test Point")
      (libsource (lib "BitMain_Miner_1") (part "TP"))
    )
    (comp (ref "TP82")
      (value "TP")
      (footprint "TP_SMD")
      (description "Test Point")
      (libsource (lib "BitMain_Miner_1") (part "TP"))
    )
    (comp (ref "TP83")
      (value "TP")
      (footprint "TP_SMD")
      (description "Test Point")
      (libsource (lib "BitMain_Miner_1") (part "TP"))
    )
    (comp (ref "TP84")
      (value "TP")
      (footprint "TP_SMD")
      (description "Test Point")
      (libsource (lib "BitMain_Miner_1") (part "TP"))
    )
    (comp (ref "TP85")
      (value "TP")
      (footprint "TP_SMD")
      (description "Test Point")
      (libsource (lib "BitMain_Miner_1") (part "TP"))
    )
    (comp (ref "TP86")
      (value "TP")
      (footprint "TP_SMD")
      (description "Test Point")
      (libsource (lib "BitMain_Miner_1") (part "TP"))
    )
    (comp (ref "TP87")
      (value "TP")
      (footprint "TP_SMD")
      (description "Test Point")
      (libsource (lib "BitMain_Miner_1") (part "TP"))
    )
    (comp (ref "TP88")
      (value "TP")
      (footprint "TP_SMD")
      (description "Test Point")
      (libsource (lib "BitMain_Miner_1") (part "TP"))
    )
    (comp (ref "U11") (value "BM1380") (footprint "QFN56") (libsource (lib "ANT_Miner_V1.3") (part "BM1380")))
    (comp (ref "U12") (value "BM1380") (footprint "QFN56") (libsource (lib "ANT_Miner_V1.3") (part "BM1380")))
    (comp (ref "U13") (value "BM1380") (footprint "QFN56") (libsource (lib "ANT_Miner_V1.3") (part "BM1380")))
    (comp (ref "U14") (value "BM1380") (footprint "QFN56") (libsource (lib "ANT_Miner_V1.3") (part "BM1380")))
    (comp (ref "U15") (value "BM1380") (footprint "QFN56") (libsource (lib "ANT_Miner_V1.3") (part "BM1380")))
    (comp (ref "U16") (value "BM1380") (footprint "QFN56") (libsource (lib "ANT_Miner_V1.3") (part "BM1380")))
    (comp (ref "U17") (value "BM1380") (footprint "QFN56") (libsource (lib "ANT_Miner_V1.3") (part "BM1380")))
    (comp (ref "U18") (value "BM1380") (footprint "QFN56") (libsource (lib "ANT_Miner_V1.3") (part "BM1380")))
  )
  (nets
    (net (code "1") (name "+3.3V") (class "Default")
      (node (ref "C164") (pin "2") (pinfunction "2_2") (pintype "passive"))
      (node (ref "C165") (pin "2") (pinfunction "2_2") (pintype "passive"))
      (node (ref "C166") (pin "2") (pinfunction "2_2") (pintype "passive"))
      (node (ref "C167") (pin "2") (pinfunction "2_2") (pintype "passive"))
      (node (ref "C168") (pin "2") (pinfunction "2_2") (pintype "passive"))
      (node (ref "C169") (pin "2") (pinfunction "2_2") (pintype "passive"))
      (node (ref "C170") (pin "2") (pinfunction "2_2") (pintype "passive"))
      (node (ref "C171") (pin "2") (pinfunction "2_2") (pintype "passive"))
      (node (ref "C172") (pin "2") (pinfunction "2_2") (pintype "passive"))
      (node (ref "C173") (pin "2") (pinfunction "2_2") (pintype "passive"))
      (node (ref "C174") (pin "2") (pinfunction "2_2") (pintype "passive"))
      (node (ref "C175") (pin "2") (pinfunction "2_2") (pintype "passive"))
      (node (ref "C228") (pin "2") (pinfunction "2_2") (pintype "passive"))
      (node (ref "C229") (pin "2") (pinfunction "2_2") (pintype "passive"))
      (node (ref "C230") (pin "2") (pinfunction "2_2") (pintype "passive"))
      (node (ref "C231") (pin "2") (pinfunction "2_2") (pintype "passive"))
      (node (ref "C232") (pin "2") (pinfunction "2_2") (pintype "passive"))
      (node (ref "C233") (pin "2") (pinfunction "2_2") (pintype "passive"))
      (node (ref "C234") (pin "2") (pinfunction "2_2") (pintype "passive"))
      (node (ref "C235") (pin "2") (pinfunction "2_2") (pintype "passive"))
      (node (ref "C236") (pin "2") (pinfunction "2_2") (pintype "passive"))
      (node (ref "C237") (pin "2") (pinfunction "2_2") (pintype "passive"))
      (node (ref "C238") (pin "2") (pinfunction "2_2") (pintype "passive"))
      (node (ref "C239") (pin "2") (pinfunction "2_2") (pintype "passive"))
      (node (ref "U11") (pin "14") (pinfunction "VCC_14") (pintype "power_in"))
      (node (ref "U11") (pin "27") (pinfunction "ADDR6_27") (pintype "passive"))
      (node (ref "U11") (pin "29") (pinfunction "VCC_29") (pintype "power_in"))
      (node (ref "U11") (pin "43") (pinfunction "VCC_43") (pintype "power_in"))
      (node (ref "U12") (pin "14") (pinfunction "VCC_14") (pintype "power_in"))
      (node (ref "U12") (pin "20") (pinfunction "ADDR3_20") (pintype "passive"))
      (node (ref "U12") (pin "27") (pinfunction "ADDR6_27") (pintype "passive"))
      (node (ref "U12") (pin "29") (pinfunction "VCC_29") (pintype "power_in"))
      (node (ref "U12") (pin "43") (pinfunction "VCC_43") (pintype "power_in"))
      (node (ref "U13") (pin "14") (pinfunction "VCC_14") (pintype "power_in"))
      (node (ref "U13") (pin "23") (pinfunction "ADDR4_23") (pintype "passive"))
      (node (ref "U13") (pin "27") (pinfunction "ADDR6_27") (pintype "passive"))
      (node (ref "U13") (pin "29") (pinfunction "VCC_29") (pintype "power_in"))
      (node (ref "U13") (pin "43") (pinfunction "VCC_43") (pintype "power_in"))
      (node (ref "U14") (pin "14") (pinfunction "VCC_14") (pintype "power_in"))
      (node (ref "U14") (pin "20") (pinfunction "ADDR3_20") (pintype "passive"))
      (node (ref "U14") (pin "23") (pinfunction "ADDR4_23") (pintype "passive"))
      (node (ref "U14") (pin "27") (pinfunction "ADDR6_27") (pintype "passive"))
      (node (ref "U14") (pin "29") (pinfunction "VCC_29") (pintype "power_in"))
      (node (ref "U14") (pin "43") (pinfunction "VCC_43") (pintype "power_in"))
      (node (ref "U15") (pin "14") (pinfunction "VCC_14") (pintype "power_in"))
      (node (ref "U15") (pin "24") (pinfunction "ADDR5_24") (pintype "passive"))
      (node (ref "U15") (pin "27") (pinfunction "ADDR6_27") (pintype "passive"))
      (node (ref "U15") (pin "29") (pinfunction "VCC_29") (pintype "power_in"))
      (node (ref "U15") (pin "43") (pinfunction "VCC_43") (pintype "power_in"))
      (node (ref "U16") (pin "14") (pinfunction "VCC_14") (pintype "power_in"))
      (node (ref "U16") (pin "20") (pinfunction "ADDR3_20") (pintype "passive"))
      (node (ref "U16") (pin "24") (pinfunction "ADDR5_24") (pintype "passive"))
      (node (ref "U16") (pin "27") (pinfunction "ADDR6_27") (pintype "passive"))
      (node (ref "U16") (pin "29") (pinfunction "VCC_29") (pintype "power_in"))
      (node (ref "U16") (pin "43") (pinfunction "VCC_43") (pintype "power_in"))
      (node (ref "U17") (pin "14") (pinfunction "VCC_14") (pintype "power_in"))
      (node (ref "U17") (pin "23") (pinfunction "ADDR4_23") (pintype "passive"))
      (node (ref "U17") (pin "24") (pinfunction "ADDR5_24") (pintype "passive"))
      (node (ref "U17") (pin "27") (pinfunction "ADDR6_27") (pintype "passive"))
      (node (ref "U17") (pin "29") (pinfunction "VCC_29") (pintype "power_in"))
      (node (ref "U17") (pin "43") (pinfunction "VCC_43") (pintype "power_in"))
      (node (ref "U18") (pin "14") (pinfunction "VCC_14") (pintype "power_in"))
      (node (ref "U18") (pin "20") (pinfunction "ADDR3_20") (pintype "passive"))
      (node (ref "U18") (pin "23") (pinfunction "ADDR4_23") (pintype "passive"))
      (node (ref "U18") (pin "24") (pinfunction "ADDR5_24") (pintype "passive"))
      (node (ref "U18") (pin "27") (pinfunction "ADDR6_27") (pintype "passive"))
      (node (ref "U18") (pin "29") (pinfunction "VCC_29") (pintype "power_in"))
      (node (ref "U18") (pin "43") (pinfunction "VCC_43") (pintype "power_in"))
    )
    (net (code "2") (name "/BO8") (class "Default")
      (node (ref "U11") (pin "9") (pinfunction "BI_9") (pintype "input"))
    )
    (net (code "3") (name "/BO9") (class "Default")
      (node (ref "TP49") (pin "1") (pinfunction "1_1") (pintype "passive"))
      (node (ref "U11") (pin "34") (pinfunction "BO_34") (pintype "output"))
      (node (ref "U12") (pin "9") (pinfunction "BI_9") (pintype "input"))
    )
    (net (code "4") (name "/BO10") (class "Default")
      (node (ref "TP50") (pin "1") (pinfunction "1_1") (pintype "passive"))
      (node (ref "U12") (pin "34") (pinfunction "BO_34") (pintype "output"))
      (node (ref "U13") (pin "9") (pinfunction "BI_9") (pintype "input"))
    )
    (net (code "5") (name "/BO11") (class "Default")
      (node (ref "TP51") (pin "1") (pinfunction "1_1") (pintype "passive"))
      (node (ref "U13") (pin "34") (pinfunction "BO_34") (pintype "output"))
      (node (ref "U14") (pin "9") (pinfunction "BI_9") (pintype "input"))
    )
    (net (code "6") (name "/BO12") (class "Default")
      (node (ref "TP52") (pin "1") (pinfunction "1_1") (pintype "passive"))
      (node (ref "U14") (pin "34") (pinfunction "BO_34") (pintype "output"))
      (node (ref "U15") (pin "9") (pinfunction "BI_9") (pintype "input"))
    )
    (net (code "7") (name "/BO13") (class "Default")
      (node (ref "TP70") (pin "1") (pinfunction "1_1") (pintype "passive"))
      (node (ref "U15") (pin "34") (pinfunction "BO_34") (pintype "output"))
      (node (ref "U16") (pin "9") (pinfunction "BI_9") (pintype "input"))
    )
    (net (code "8") (name "/BO14") (class "Default")
      (node (ref "TP71") (pin "1") (pinfunction "1_1") (pintype "passive"))
      (node (ref "U16") (pin "34") (pinfunction "BO_34") (pintype "output"))
      (node (ref "U17") (pin "9") (pinfunction "BI_9") (pintype "input"))
    )
    (net (code "9") (name "/BO15") (class "Default")
      (node (ref "TP72") (pin "1") (pinfunction "1_1") (pintype "passive"))
      (node (ref "U17") (pin "34") (pinfunction "BO_34") (pintype "output"))
      (node (ref "U18") (pin "9") (pinfunction "BI_9") (pintype "input"))
    )
    (net (code "10") (name "/BO16") (class "Default")
      (node (ref "TP69") (pin "1") (pinfunction "1_1") (pintype "passive"))
      (node (ref "U18") (pin "34") (pinfunction "BO_34") (pintype "output"))
    )
    (net (code "11") (name "/CLK8") (class "Default")
      (node (ref "U11") (pin "1") (pinfunction "XIN_1") (pintype "input"))
    )
    (net (code "12") (name "/CLK9") (class "Default")
      (node (ref "TP62") (pin "1") (pinfunction "1_1") (pintype "passive"))
      (node (ref "U11") (pin "39") (pinfunction "CLKOUT_39") (pintype "output"))
      (node (ref "U12") (pin "1") (pinfunction "XIN_1") (pintype "input"))
    )
    (net (code "13") (name "/CLK10") (class "Default")
      (node (ref "TP64") (pin "1") (pinfunction "1_1") (pintype "passive"))
      (node (ref "U12") (pin "39") (pinfunction "CLKOUT_39") (pintype "output"))
      (node (ref "U13") (pin "1") (pinfunction "XIN_1") (pintype "input"))
    )
    (net (code "14") (name "/CLK11") (class "Default")
      (node (ref "TP66") (pin "1") (pinfunction "1_1") (pintype "passive"))
      (node (ref "U13") (pin "39") (pinfunction "CLKOUT_39") (pintype "output"))
      (node (ref "U14") (pin "1") (pinfunction "XIN_1") (pintype "input"))
    )
    (net (code "15") (name "/CLK12") (class "Default")
      (node (ref "TP68") (pin "1") (pinfunction "1_1") (pintype "passive"))
      (node (ref "U14") (pin "39") (pinfunction "CLKOUT_39") (pintype "output"))
      (node (ref "U15") (pin "1") (pinfunction "XIN_1") (pintype "input"))
    )
    (net (code "16") (name "/CLK13") (class "Default")
      (node (ref "TP84") (pin "1") (pinfunction "1_1") (pintype "passive"))
      (node (ref "U15") (pin "39") (pinfunction "CLKOUT_39") (pintype "output"))
      (node (ref "U16") (pin "1") (pinfunction "XIN_1") (pintype "input"))
    )
    (net (code "17") (name "/CLK14") (class "Default")
      (node (ref "TP86") (pin "1") (pinfunction "1_1") (pintype "passive"))
      (node (ref "U16") (pin "39") (pinfunction "CLKOUT_39") (pintype "output"))
      (node (ref "U17") (pin "1") (pinfunction "XIN_1") (pintype "input"))
    )
    (net (code "18") (name "/CLK15") (class "Default")
      (node (ref "TP88") (pin "1") (pinfunction "1_1") (pintype "passive"))
      (node (ref "U17") (pin "39") (pinfunction "CLKOUT_39") (pintype "output"))
      (node (ref "U18") (pin "1") (pinfunction "XIN_1") (pintype "input"))
    )
    (net (code "19") (name "/CLK16") (class "Default")
      (node (ref "TP82") (pin "1") (pinfunction "1_1") (pintype "passive"))
      (node (ref "U18") (pin "39") (pinfunction "CLKOUT_39") (pintype "output"))
    )
    (net (code "20") (name "/CO8") (class "Default")
      (node (ref "U11") (pin "5") (pinfunction "CI_5") (pintype "input"))
    )
    (net (code "21") (name "/CO9") (class "Default")
      (node (ref "TP53") (pin "1") (pinfunction "1_1") (pintype "passive"))
      (node (ref "U11") (pin "38") (pinfunction "CO_38") (pintype "output"))
      (node (ref "U12") (pin "5") (pinfunction "CI_5") (pintype "input"))
    )
    (net (code "22") (name "/CO10") (class "Default")
      (node (ref "TP55") (pin "1") (pinfunction "1_1") (pintype "passive"))
      (node (ref "U12") (pin "38") (pinfunction "CO_38") (pintype "output"))
      (node (ref "U13") (pin "5") (pinfunction "CI_5") (pintype "input"))
    )
    (net (code "23") (name "/CO11") (class "Default")
      (node (ref "TP57") (pin "1") (pinfunction "1_1") (pintype "passive"))
      (node (ref "U13") (pin "38") (pinfunction "CO_38") (pintype "output"))
      (node (ref "U14") (pin "5") (pinfunction "CI_5") (pintype "input"))
    )
    (net (code "24") (name "/CO12") (class "Default")
      (node (ref "TP59") (pin "1") (pinfunction "1_1") (pintype "passive"))
      (node (ref "U14") (pin "38") (pinfunction "CO_38") (pintype "output"))
      (node (ref "U15") (pin "5") (pinfunction "CI_5") (pintype "input"))
    )
    (net (code "25") (name "/CO13") (class "Default")
      (node (ref "TP75") (pin "1") (pinfunction "1_1") (pintype "passive"))
      (node (ref "U15") (pin "38") (pinfunction "CO_38") (pintype "output"))
      (node (ref "U16") (pin "5") (pinfunction "CI_5") (pintype "input"))
    )
    (net (code "26") (name "/CO14") (class "Default")
      (node (ref "TP77") (pin "1") (pinfunction "1_1") (pintype "passive"))
      (node (ref "U16") (pin "38") (pinfunction "CO_38") (pintype "output"))
      (node (ref "U17") (pin "5") (pinfunction "CI_5") (pintype "input"))
    )
    (net (code "27") (name "/CO15") (class "Default")
      (node (ref "TP79") (pin "1") (pinfunction "1_1") (pintype "passive"))
      (node (ref "U17") (pin "38") (pinfunction "CO_38") (pintype "output"))
      (node (ref "U18") (pin "5") (pinfunction "CI_5") (pintype "input"))
    )
    (net (code "28") (name "/CO16") (class "Default")
      (node (ref "TP73") (pin "1") (pinfunction "1_1") (pintype "passive"))
      (node (ref "U18") (pin "38") (pinfunction "CO_38") (pintype "output"))
    )
    (net (code "29") (name "/RI8") (class "Default")
      (node (ref "U11") (pin "6") (pinfunction "RO_6") (pintype "output"))
    )
    (net (code "30") (name "/RI9") (class "Default")
      (node (ref "TP54") (pin "1") (pinfunction "1_1") (pintype "passive"))
      (node (ref "U11") (pin "37") (pinfunction "RI_37") (pintype "input"))
      (node (ref "U12") (pin "6") (pinfunction "RO_6") (pintype "output"))
    )
    (net (code "31") (name "/RI10") (class "Default")
      (node (ref "TP56") (pin "1") (pinfunction "1_1") (pintype "passive"))
      (node (ref "U12") (pin "37") (pinfunction "RI_37") (pintype "input"))
      (node (ref "U13") (pin "6") (pinfunction "RO_6") (pintype "output"))
    )
    (net (code "32") (name "/RI11") (class "Default")
      (node (ref "TP58") (pin "1") (pinfunction "1_1") (pintype "passive"))
      (node (ref "U13") (pin "37") (pinfunction "RI_37") (pintype "input"))
      (node (ref "U14") (pin "6") (pinfunction "RO_6") (pintype "output"))
    )
    (net (code "33") (name "/RI12") (class "Default")
      (node (ref "TP60") (pin "1") (pinfunction "1_1") (pintype "passive"))
      (node (ref "U14") (pin "37") (pinfunction "RI_37") (pintype "input"))
      (node (ref "U15") (pin "6") (pinfunction "RO_6") (pintype "output"))
    )
    (net (code "34") (name "/RI13") (class "Default")
      (node (ref "TP76") (pin "1") (pinfunction "1_1") (pintype "passive"))
      (node (ref "U15") (pin "37") (pinfunction "RI_37") (pintype "input"))
      (node (ref "U16") (pin "6") (pinfunction "RO_6") (pintype "output"))
    )
    (net (code "35") (name "/RI14") (class "Default")
      (node (ref "TP78") (pin "1") (pinfunction "1_1") (pintype "passive"))
      (node (ref "U16") (pin "37") (pinfunction "RI_37") (pintype "input"))
      (node (ref "U17") (pin "6") (pinfunction "RO_6") (pintype "output"))
    )
    (net (code "36") (name "/RI15") (class "Default")
      (node (ref "TP80") (pin "1") (pinfunction "1_1") (pintype "passive"))
      (node (ref "U17") (pin "37") (pinfunction "RI_37") (pintype "input"))
      (node (ref "U18") (pin "6") (pinfunction "RO_6") (pintype "output"))
    )
    (net (code "37") (name "/RI16") (class "Default")
      (node (ref "TP74") (pin "1") (pinfunction "1_1") (pintype "passive"))
      (node (ref "U18") (pin "37") (pinfunction "RI_37") (pintype "input"))
    )
    (net (code "38") (name "/RST8") (class "Default")
      (node (ref "U11") (pin "10") (pinfunction "RST_N_10") (pintype "input"))
    )
    (net (code "39") (name "/RST9") (class "Default")
      (node (ref "TP61") (pin "1") (pinfunction "1_1") (pintype "passive"))
      (node (ref "U11") (pin "33") (pinfunction "NRSTO_33") (pintype "output"))
      (node (ref "U12") (pin "10") (pinfunction "RST_N_10") (pintype "input"))
    )
    (net (code "40") (name "/RST10") (class "Default")
      (node (ref "TP63") (pin "1") (pinfunction "1_1") (pintype "passive"))
      (node (ref "U12") (pin "33") (pinfunction "NRSTO_33") (pintype "output"))
      (node (ref "U13") (pin "10") (pinfunction "RST_N_10") (pintype "input"))
    )
    (net (code "41") (name "/RST11") (class "Default")
      (node (ref "TP65") (pin "1") (pinfunction "1_1") (pintype "passive"))
      (node (ref "U13") (pin "33") (pinfunction "NRSTO_33") (pintype "output"))
      (node (ref "U14") (pin "10") (pinfunction "RST_N_10") (pintype "input"))
    )
    (net (code "42") (name "/RST12") (class "Default")
      (node (ref "TP67") (pin "1") (pinfunction "1_1") (pintype "passive"))
      (node (ref "U14") (pin "33") (pinfunction "NRSTO_33") (pintype "output"))
      (node (ref "U15") (pin "10") (pinfunction "RST_N_10") (pintype "input"))
    )
    (net (code "43") (name "/RST13") (class "Default")
      (node (ref "TP83") (pin "1") (pinfunction "1_1") (pintype "passive"))
      (node (ref "U15") (pin "33") (pinfunction "NRSTO_33") (pintype "output"))
      (node (ref "U16") (pin "10") (pinfunction "RST_N_10") (pintype "input"))
    )
    (net (code "44") (name "/RST14") (class "Default")
      (node (ref "TP85") (pin "1") (pinfunction "1_1") (pintype "passive"))
      (node (ref "U16") (pin "33") (pinfunction "NRSTO_33") (pintype "output"))
      (node (ref "U17") (pin "10") (pinfunction "RST_N_10") (pintype "input"))
    )
    (net (code "45") (name "/RST15") (class "Default")
      (node (ref "TP87") (pin "1") (pinfunction "1_1") (pintype "passive"))
      (node (ref "U17") (pin "33") (pinfunction "NRSTO_33") (pintype "output"))
      (node (ref "U18") (pin "10") (pinfunction "RST_N_10") (pintype "input"))
    )
    (net (code "46") (name "/RST16") (class "Default")
      (node (ref "TP81") (pin "1") (pinfunction "1_1") (pintype "passive"))
      (node (ref "U18") (pin "33") (pinfunction "NRSTO_33") (pintype "output"))
    )
    (net (code "47") (name "GND") (class "Default")
      (node (ref "C152") (pin "2") (pinfunction "2_2") (pintype "passive"))
      (node (ref "C153") (pin "2") (pinfunction "2_2") (pintype "passive"))
      (node (ref "C154") (pin "1") (pinfunction "1_1") (pintype "passive"))
      (node (ref "C155") (pin "1") (pinfunction "1_1") (pintype "passive"))
      (node (ref "C156") (pin "2") (pinfunction "2_2") (pintype "passive"))
      (node (ref "C157") (pin "1") (pinfunction "1_1") (pintype "passive"))
      (node (ref "C158") (pin "2") (pinfunction "2_2") (pintype "passive"))
      (node (ref "C159") (pin "1") (pinfunction "1_1") (pintype "passive"))
      (node (ref "C160") (pin "2") (pinfunction "2_2") (pintype "passive"))
      (node (ref "C161") (pin "1") (pinfunction "1_1") (pintype "passive"))
      (node (ref "C162") (pin "2") (pinfunction "2_2") (pintype "passive"))
      (node (ref "C163") (pin "1") (pinfunction "1_1") (pintype "passive"))
      (node (ref "C164") (pin "1") (pinfunction "1_1") (pintype "passive"))
      (node (ref "C165") (pin "1") (pinfunction "1_1") (pintype "passive"))
      (node (ref "C166") (pin "1") (pinfunction "1_1") (pintype "passive"))
      (node (ref "C167") (pin "1") (pinfunction "1_1") (pintype "passive"))
      (node (ref "C168") (pin "1") (pinfunction "1_1") (pintype "passive"))
      (node (ref "C169") (pin "1") (pinfunction "1_1") (pintype "passive"))
      (node (ref "C170") (pin "1") (pinfunction "1_1") (pintype "passive"))
      (node (ref "C171") (pin "1") (pinfunction "1_1") (pintype "passive"))
      (node (ref "C172") (pin "1") (pinfunction "1_1") (pintype "passive"))
      (node (ref "C173") (pin "1") (pinfunction "1_1") (pintype "passive"))
      (node (ref "C174") (pin "1") (pinfunction "1_1") (pintype "passive"))
      (node (ref "C175") (pin "1") (pinfunction "1_1") (pintype "passive"))
      (node (ref "C176") (pin "1") (pinfunction "1_1") (pintype "passive"))
      (node (ref "C177") (pin "1") (pinfunction "1_1") (pintype "passive"))
      (node (ref "C178") (pin "1") (pinfunction "1_1") (pintype "passive"))
      (node (ref "C179") (pin "1") (pinfunction "1_1") (pintype "passive"))
      (node (ref "C180") (pin "1") (pinfunction "1_1") (pintype "passive"))
      (node (ref "C181") (pin "1") (pinfunction "1_1") (pintype "passive"))
      (node (ref "C182") (pin "1") (pinfunction "1_1") (pintype "passive"))
      (node (ref "C183") (pin "1") (pinfunction "1_1") (pintype "passive"))
      (node (ref "C184") (pin "1") (pinfunction "1_1") (pintype "passive"))
      (node (ref "C185") (pin "1") (pinfunction "1_1") (pintype "passive"))
      (node (ref "C186") (pin "1") (pinfunction "1_1") (pintype "passive"))
      (node (ref "C187") (pin "1") (pinfunction "1_1") (pintype "passive"))
      (node (ref "C188") (pin "1") (pinfunction "1_1") (pintype "passive"))
      (node (ref "C189") (pin "1") (pinfunction "1_1") (pintype "passive"))
      (node (ref "C190") (pin "1") (pinfunction "1_1") (pintype "passive"))
      (node (ref "C191") (pin "1") (pinfunction "1_1") (pintype "passive"))
      (node (ref "C192") (pin "1") (pinfunction "1_1") (pintype "passive"))
      (node (ref "C193") (pin "1") (pinfunction "1_1") (pintype "passive"))
      (node (ref "C194") (pin "1") (pinfunction "1_1") (pintype "passive"))
      (node (ref "C195") (pin "1") (pinfunction "1_1") (pintype "passive"))
      (node (ref "C196") (pin "1") (pinfunction "1_1") (pintype "passive"))
      (node (ref "C197") (pin "1") (pinfunction "1_1") (pintype "passive"))
      (node (ref "C198") (pin "1") (pinfunction "1_1") (pintype "passive"))
      (node (ref "C199") (pin "1") (pinfunction "1_1") (pintype "passive"))
      (node (ref "C200") (pin "1") (pinfunction "1_1") (pintype "passive"))
      (node (ref "C201") (pin "1") (pinfunction "1_1") (pintype "passive"))
      (node (ref "C202") (pin "1") (pinfunction "1_1") (pintype "passive"))
      (node (ref "C203") (pin "1") (pinfunction "1_1") (pintype "passive"))
      (node (ref "C204") (pin "1") (pinfunction "1_1") (pintype "passive"))
      (node (ref "C205") (pin "1") (pinfunction "1_1") (pintype "passive"))
      (node (ref "C206") (pin "1") (pinfunction "1_1") (pintype "passive"))
      (node (ref "C207") (pin "1") (pinfunction "1_1") (pintype "passive"))
      (node (ref "C208") (pin "1") (pinfunction "1_1") (pintype "passive"))
      (node (ref "C209") (pin "1") (pinfunction "1_1") (pintype "passive"))
      (node (ref "C210") (pin "1") (pinfunction "1_1") (pintype "passive"))
      (node (ref "C211") (pin "1") (pinfunction "1_1") (pintype "passive"))
      (node (ref "C212") (pin "1") (pinfunction "1_1") (pintype "passive"))
      (node (ref "C213") (pin "1") (pinfunction "1_1") (pintype "passive"))
      (node (ref "C214") (pin "1") (pinfunction "1_1") (pintype "passive"))
      (node (ref "C215") (pin "1") (pinfunction "1_1") (pintype "passive"))
      (node (ref "C216") (pin "1") (pinfunction "1_1") (pintype "passive"))
      (node (ref "C217") (pin "1") (pinfunction "1_1") (pintype "passive"))
      (node (ref "C218") (pin "1") (pinfunction "1_1") (pintype "passive"))
      (node (ref "C219") (pin "1") (pinfunction "1_1") (pintype "passive"))
      (node (ref "C220") (pin "2") (pinfunction "2_2") (pintype "passive"))
      (node (ref "C221") (pin "1") (pinfunction "1_1") (pintype "passive"))
      (node (ref "C222") (pin "2") (pinfunction "2_2") (pintype "passive"))
      (node (ref "C223") (pin "1") (pinfunction "1_1") (pintype "passive"))
      (node (ref "C224") (pin "2") (pinfunction "2_2") (pintype "passive"))
      (node (ref "C225") (pin "1") (pinfunction "1_1") (pintype "passive"))
      (node (ref "C226") (pin "2") (pinfunction "2_2") (pintype "passive"))
      (node (ref "C227") (pin "1") (pinfunction "1_1") (pintype "passive"))
      (node (ref "C228") (pin "1") (pinfunction "1_1") (pintype "passive"))
      (node (ref "C229") (pin "1") (pinfunction "1_1") (pintype "passive"))
      (node (ref "C230") (pin "1") (pinfunction "1_1") (pintype "passive"))
      (node (ref "C231") (pin "1") (pinfunction "1_1") (pintype "passive"))
      (node (ref "C232") (pin "1") (pinfunction "1_1") (pintype "passive"))
      (node (ref "C233") (pin "1") (pinfunction "1_1") (pintype "passive"))
      (node (ref "C234") (pin "1") (pinfunction "1_1") (pintype "passive"))
      (node (ref "C235") (pin "1") (pinfunction "1_1") (pintype "passive"))
      (node (ref "C236") (pin "1") (pinfunction "1_1") (pintype "passive"))
      (node (ref "C237") (pin "1") (pinfunction "1_1") (pintype "passive"))
      (node (ref "C238") (pin "1") (pinfunction "1_1") (pintype "passive"))
      (node (ref "C239") (pin "1") (pinfunction "1_1") (pintype "passive"))
      (node (ref "C240") (pin "1") (pinfunction "1_1") (pintype "passive"))
      (node (ref "C241") (pin "1") (pinfunction "1_1") (pintype "passive"))
      (node (ref "C242") (pin "1") (pinfunction "1_1") (pintype "passive"))
      (node (ref "C243") (pin "1") (pinfunction "1_1") (pintype "passive"))
      (node (ref "C244") (pin "1") (pinfunction "1_1") (pintype "passive"))
      (node (ref "C245") (pin "1") (pinfunction "1_1") (pintype "passive"))
      (node (ref "C246") (pin "1") (pinfunction "1_1") (pintype "passive"))
      (node (ref "C247") (pin "1") (pinfunction "1_1") (pintype "passive"))
      (node (ref "C248") (pin "1") (pinfunction "1_1") (pintype "passive"))
      (node (ref "C249") (pin "1") (pinfunction "1_1") (pintype "passive"))
      (node (ref "C250") (pin "1") (pinfunction "1_1") (pintype "passive"))
      (node (ref "C251") (pin "1") (pinfunction "1_1") (pintype "passive"))
      (node (ref "C252") (pin "1") (pinfunction "1_1") (pintype "passive"))
      (node (ref "C253") (pin "1") (pinfunction "1_1") (pintype "passive"))
      (node (ref "C254") (pin "1") (pinfunction "1_1") (pintype "passive"))
      (node (ref "C255") (pin "1") (pinfunction "1_1") (pintype "passive"))
      (node (ref "C256") (pin "1") (pinfunction "1_1") (pintype "passive"))
      (node (ref "C257") (pin "1") (pinfunction "1_1") (pintype "passive"))
      (node (ref "C258") (pin "1") (pinfunction "1_1") (pintype "passive"))
      (node (ref "C259") (pin "1") (pinfunction "1_1") (pintype "passive"))
      (node (ref "C260") (pin "1") (pinfunction "1_1") (pintype "passive"))
      (node (ref "C261") (pin "1") (pinfunction "1_1") (pintype "passive"))
      (node (ref "C262") (pin "1") (pinfunction "1_1") (pintype "passive"))
      (node (ref "C263") (pin "1") (pinfunction "1_1") (pintype "passive"))
      (node (ref "C264") (pin "1") (pinfunction "1_1") (pintype "passive"))
      (node (ref "C265") (pin "1") (pinfunction "1_1") (pintype "passive"))
      (node (ref "C266") (pin "1") (pinfunction "1_1") (pintype "passive"))
      (node (ref "C267") (pin "1") (pinfunction "1_1") (pintype "passive"))
      (node (ref "C268") (pin "1") (pinfunction "1_1") (pintype "passive"))
      (node (ref "C269") (pin "1") (pinfunction "1_1") (pintype "passive"))
      (node (ref "C270") (pin "1") (pinfunction "1_1") (pintype "passive"))
      (node (ref "C271") (pin "1") (pinfunction "1_1") (pintype "passive"))
      (node (ref "C272") (pin "1") (pinfunction "1_1") (pintype "passive"))
      (node (ref "C273") (pin "1") (pinfunction "1_1") (pintype "passive"))
      (node (ref "C274") (pin "1") (pinfunction "1_1") (pintype "passive"))
      (node (ref "C275") (pin "1") (pinfunction "1_1") (pintype "passive"))
      (node (ref "C276") (pin "1") (pinfunction "1_1") (pintype "passive"))
      (node (ref "C277") (pin "1") (pinfunction "1_1") (pintype "passive"))
      (node (ref "C278") (pin "1") (pinfunction "1_1") (pintype "passive"))
      (node (ref "C279") (pin "1") (pinfunction "1_1") (pintype "passive"))
      (node (ref "C280") (pin "1") (pinfunction "1_1") (pintype "passive"))
      (node (ref "C281") (pin "1") (pinfunction "1_1") (pintype "passive"))
      (node (ref "C282") (pin "1") (pinfunction "1_1") (pintype "passive"))
      (node (ref "C283") (pin "1") (pinfunction "1_1") (pintype "passive"))
      (node (ref "M10") (pin "0") (pinfunction "PIN_0") (pintype "power_in"))
      (node (ref "M11") (pin "0") (pinfunction "PIN_0") (pintype "power_in"))
      (node (ref "M12") (pin "0") (pinfunction "PIN_0") (pintype "power_in"))
      (node (ref "M13") (pin "0") (pinfunction "PIN_0") (pintype "power_in"))
      (node (ref "M9") (pin "0") (pinfunction "PIN_0") (pintype "power_in"))
      (node (ref "U11") (pin "12") (pinfunction "GND_12") (pintype "power_in"))
      (node (ref "U11") (pin "13") (pinfunction "VSS_13") (pintype "power_in"))
      (node (ref "U11") (pin "15") (pinfunction "ADDR0_15") (pintype "passive"))
      (node (ref "U11") (pin "16") (pinfunction "ADDR1_16") (pintype "passive"))
      (node (ref "U11") (pin "18") (pinfunction "GND_18") (pintype "power_in"))
      (node (ref "U11") (pin "19") (pinfunction "ADDR2_19") (pintype "passive"))
      (node (ref "U11") (pin "20") (pinfunction "ADDR3_20") (pintype "passive"))
      (node (ref "U11") (pin "22") (pinfunction "GND_22") (pintype "power_in"))
      (node (ref "U11") (pin "23") (pinfunction "ADDR4_23") (pintype "passive"))
      (node (ref "U11") (pin "24") (pinfunction "ADDR5_24") (pintype "passive"))
      (node (ref "U11") (pin "26") (pinfunction "GND_26") (pintype "power_in"))
      (node (ref "U11") (pin "28") (pinfunction "ADDR7_28") (pintype "passive"))
      (node (ref "U11") (pin "3") (pinfunction "GND_3") (pintype "power_in"))
      (node (ref "U11") (pin "30") (pinfunction "VSS_30") (pintype "power_in"))
      (node (ref "U11") (pin "31") (pinfunction "GND_31") (pintype "power_in"))
      (node (ref "U11") (pin "35") (pinfunction "GND_35") (pintype "power_in"))
      (node (ref "U11") (pin "41") (pinfunction "GND_41") (pintype "power_in"))
      (node (ref "U11") (pin "42") (pinfunction "VSS_42") (pintype "power_in"))
      (node (ref "U11") (pin "45") (pinfunction "SMODE_45") (pintype "passive"))
      (node (ref "U11") (pin "46") (pinfunction "GND_46") (pintype "power_in"))
      (node (ref "U11") (pin "50") (pinfunction "TEST_50") (pintype "passive"))
      (node (ref "U11") (pin "52") (pinfunction "GND_52") (pintype "power_in"))
      (node (ref "U11") (pin "53") (pinfunction "PLL_DVSS_53") (pintype "power_in"))
      (node (ref "U11") (pin "56") (pinfunction "PLL_AVSS_56") (pintype "power_in"))
      (node (ref "U11") (pin "57") (pinfunction "GND_57") (pintype "power_in"))
      (node (ref "U11") (pin "8") (pinfunction "GND_8") (pintype "power_in"))
      (node (ref "U12") (pin "12") (pinfunction "GND_12") (pintype "power_in"))
      (node (ref "U12") (pin "13") (pinfunction "VSS_13") (pintype "power_in"))
      (node (ref "U12") (pin "15") (pinfunction "ADDR0_15") (pintype "passive"))
      (node (ref "U12") (pin "16") (pinfunction "ADDR1_16") (pintype "passive"))
      (node (ref "U12") (pin "18") (pinfunction "GND_18") (pintype "power_in"))
      (node (ref "U12") (pin "19") (pinfunction "ADDR2_19") (pintype "passive"))
      (node (ref "U12") (pin "22") (pinfunction "GND_22") (pintype "power_in"))
      (node (ref "U12") (pin "23") (pinfunction "ADDR4_23") (pintype "passive"))
      (node (ref "U12") (pin "24") (pinfunction "ADDR5_24") (pintype "passive"))
      (node (ref "U12") (pin "26") (pinfunction "GND_26") (pintype "power_in"))
      (node (ref "U12") (pin "28") (pinfunction "ADDR7_28") (pintype "passive"))
      (node (ref "U12") (pin "3") (pinfunction "GND_3") (pintype "power_in"))
      (node (ref "U12") (pin "30") (pinfunction "VSS_30") (pintype "power_in"))
      (node (ref "U12") (pin "31") (pinfunction "GND_31") (pintype "power_in"))
      (node (ref "U12") (pin "35") (pinfunction "GND_35") (pintype "power_in"))
      (node (ref "U12") (pin "41") (pinfunction "GND_41") (pintype "power_in"))
      (node (ref "U12") (pin "42") (pinfunction "VSS_42") (pintype "power_in"))
      (node (ref "U12") (pin "45") (pinfunction "SMODE_45") (pintype "passive"))
      (node (ref "U12") (pin "46") (pinfunction "GND_46") (pintype "power_in"))
      (node (ref "U12") (pin "50") (pinfunction "TEST_50") (pintype "passive"))
      (node (ref "U12") (pin "52") (pinfunction "GND_52") (pintype "power_in"))
      (node (ref "U12") (pin "53") (pinfunction "PLL_DVSS_53") (pintype "power_in"))
      (node (ref "U12") (pin "56") (pinfunction "PLL_AVSS_56") (pintype "power_in"))
      (node (ref "U12") (pin "57") (pinfunction "GND_57") (pintype "power_in"))
      (node (ref "U12") (pin "8") (pinfunction "GND_8") (pintype "power_in"))
      (node (ref "U13") (pin "12") (pinfunction "GND_12") (pintype "power_in"))
      (node (ref "U13") (pin "13") (pinfunction "VSS_13") (pintype "power_in"))
      (node (ref "U13") (pin "15") (pinfunction "ADDR0_15") (pintype "passive"))
      (node (ref "U13") (pin "16") (pinfunction "ADDR1_16") (pintype "passive"))
      (node (ref "U13") (pin "18") (pinfunction "GND_18") (pintype "power_in"))
      (node (ref "U13") (pin "19") (pinfunction "ADDR2_19") (pintype "passive"))
      (node (ref "U13") (pin "20") (pinfunction "ADDR3_20") (pintype "passive"))
      (node (ref "U13") (pin "22") (pinfunction "GND_22") (pintype "power_in"))
      (node (ref "U13") (pin "24") (pinfunction "ADDR5_24") (pintype "passive"))
      (node (ref "U13") (pin "26") (pinfunction "GND_26") (pintype "power_in"))
      (node (ref "U13") (pin "28") (pinfunction "ADDR7_28") (pintype "passive"))
      (node (ref "U13") (pin "3") (pinfunction "GND_3") (pintype "power_in"))
      (node (ref "U13") (pin "30") (pinfunction "VSS_30") (pintype "power_in"))
      (node (ref "U13") (pin "31") (pinfunction "GND_31") (pintype "power_in"))
      (node (ref "U13") (pin "35") (pinfunction "GND_35") (pintype "power_in"))
      (node (ref "U13") (pin "41") (pinfunction "GND_41") (pintype "power_in"))
      (node (ref "U13") (pin "42") (pinfunction "VSS_42") (pintype "power_in"))
      (node (ref "U13") (pin "45") (pinfunction "SMODE_45") (pintype "passive"))
      (node (ref "U13") (pin "46") (pinfunction "GND_46") (pintype "power_in"))
      (node (ref "U13") (pin "50") (pinfunction "TEST_50") (pintype "passive"))
      (node (ref "U13") (pin "52") (pinfunction "GND_52") (pintype "power_in"))
      (node (ref "U13") (pin "53") (pinfunction "PLL_DVSS_53") (pintype "power_in"))
      (node (ref "U13") (pin "56") (pinfunction "PLL_AVSS_56") (pintype "power_in"))
      (node (ref "U13") (pin "57") (pinfunction "GND_57") (pintype "power_in"))
      (node (ref "U13") (pin "8") (pinfunction "GND_8") (pintype "power_in"))
      (node (ref "U14") (pin "12") (pinfunction "GND_12") (pintype "power_in"))
      (node (ref "U14") (pin "13") (pinfunction "VSS_13") (pintype "power_in"))
      (node (ref "U14") (pin "15") (pinfunction "ADDR0_15") (pintype "passive"))
      (node (ref "U14") (pin "16") (pinfunction "ADDR1_16") (pintype "passive"))
      (node (ref "U14") (pin "18") (pinfunction "GND_18") (pintype "power_in"))
      (node (ref "U14") (pin "19") (pinfunction "ADDR2_19") (pintype "passive"))
      (node (ref "U14") (pin "22") (pinfunction "GND_22") (pintype "power_in"))
      (node (ref "U14") (pin "24") (pinfunction "ADDR5_24") (pintype "passive"))
      (node (ref "U14") (pin "26") (pinfunction "GND_26") (pintype "power_in"))
      (node (ref "U14") (pin "28") (pinfunction "ADDR7_28") (pintype "passive"))
      (node (ref "U14") (pin "3") (pinfunction "GND_3") (pintype "power_in"))
      (node (ref "U14") (pin "30") (pinfunction "VSS_30") (pintype "power_in"))
      (node (ref "U14") (pin "31") (pinfunction "GND_31") (pintype "power_in"))
      (node (ref "U14") (pin "35") (pinfunction "GND_35") (pintype "power_in"))
      (node (ref "U14") (pin "41") (pinfunction "GND_41") (pintype "power_in"))
      (node (ref "U14") (pin "42") (pinfunction "VSS_42") (pintype "power_in"))
      (node (ref "U14") (pin "45") (pinfunction "SMODE_45") (pintype "passive"))
      (node (ref "U14") (pin "46") (pinfunction "GND_46") (pintype "power_in"))
      (node (ref "U14") (pin "50") (pinfunction "TEST_50") (pintype "passive"))
      (node (ref "U14") (pin "52") (pinfunction "GND_52") (pintype "power_in"))
      (node (ref "U14") (pin "53") (pinfunction "PLL_DVSS_53") (pintype "power_in"))
      (node (ref "U14") (pin "56") (pinfunction "PLL_AVSS_56") (pintype "power_in"))
      (node (ref "U14") (pin "57") (pinfunction "GND_57") (pintype "power_in"))
      (node (ref "U14") (pin "8") (pinfunction "GND_8") (pintype "power_in"))
      (node (ref "U15") (pin "12") (pinfunction "GND_12") (pintype "power_in"))
      (node (ref "U15") (pin "13") (pinfunction "VSS_13") (pintype "power_in"))
      (node (ref "U15") (pin "15") (pinfunction "ADDR0_15") (pintype "passive"))
      (node (ref "U15") (pin "16") (pinfunction "ADDR1_16") (pintype "passive"))
      (node (ref "U15") (pin "18") (pinfunction "GND_18") (pintype "power_in"))
      (node (ref "U15") (pin "19") (pinfunction "ADDR2_19") (pintype "passive"))
      (node (ref "U15") (pin "20") (pinfunction "ADDR3_20") (pintype "passive"))
      (node (ref "U15") (pin "22") (pinfunction "GND_22") (pintype "power_in"))
      (node (ref "U15") (pin "23") (pinfunction "ADDR4_23") (pintype "passive"))
      (node (ref "U15") (pin "26") (pinfunction "GND_26") (pintype "power_in"))
      (node (ref "U15") (pin "28") (pinfunction "ADDR7_28") (pintype "passive"))
      (node (ref "U15") (pin "3") (pinfunction "GND_3") (pintype "power_in"))
      (node (ref "U15") (pin "30") (pinfunction "VSS_30") (pintype "power_in"))
      (node (ref "U15") (pin "31") (pinfunction "GND_31") (pintype "power_in"))
      (node (ref "U15") (pin "35") (pinfunction "GND_35") (pintype "power_in"))
      (node (ref "U15") (pin "41") (pinfunction "GND_41") (pintype "power_in"))
      (node (ref "U15") (pin "42") (pinfunction "VSS_42") (pintype "power_in"))
      (node (ref "U15") (pin "45") (pinfunction "SMODE_45") (pintype "passive"))
      (node (ref "U15") (pin "46") (pinfunction "GND_46") (pintype "power_in"))
      (node (ref "U15") (pin "50") (pinfunction "TEST_50") (pintype "passive"))
      (node (ref "U15") (pin "52") (pinfunction "GND_52") (pintype "power_in"))
      (node (ref "U15") (pin "53") (pinfunction "PLL_DVSS_53") (pintype "power_in"))
      (node (ref "U15") (pin "56") (pinfunction "PLL_AVSS_56") (pintype "power_in"))
      (node (ref "U15") (pin "57") (pinfunction "GND_57") (pintype "power_in"))
      (node (ref "U15") (pin "8") (pinfunction "GND_8") (pintype "power_in"))
      (node (ref "U16") (pin "12") (pinfunction "GND_12") (pintype "power_in"))
      (node (ref "U16") (pin "13") (pinfunction "VSS_13") (pintype "power_in"))
      (node (ref "U16") (pin "15") (pinfunction "ADDR0_15") (pintype "passive"))
      (node (ref "U16") (pin "16") (pinfunction "ADDR1_16") (pintype "passive"))
      (node (ref "U16") (pin "18") (pinfunction "GND_18") (pintype "power_in"))
      (node (ref "U16") (pin "19") (pinfunction "ADDR2_19") (pintype "passive"))
      (node (ref "U16") (pin "22") (pinfunction "GND_22") (pintype "power_in"))
      (node (ref "U16") (pin "23") (pinfunction "ADDR4_23") (pintype "passive"))
      (node (ref "U16") (pin "26") (pinfunction "GND_26") (pintype "power_in"))
      (node (ref "U16") (pin "28") (pinfunction "ADDR7_28") (pintype "passive"))
      (node (ref "U16") (pin "3") (pinfunction "GND_3") (pintype "power_in"))
      (node (ref "U16") (pin "30") (pinfunction "VSS_30") (pintype "power_in"))
      (node (ref "U16") (pin "31") (pinfunction "GND_31") (pintype "power_in"))
      (node (ref "U16") (pin "35") (pinfunction "GND_35") (pintype "power_in"))
      (node (ref "U16") (pin "41") (pinfunction "GND_41") (pintype "power_in"))
      (node (ref "U16") (pin "42") (pinfunction "VSS_42") (pintype "power_in"))
      (node (ref "U16") (pin "45") (pinfunction "SMODE_45") (pintype "passive"))
      (node (ref "U16") (pin "46") (pinfunction "GND_46") (pintype "power_in"))
      (node (ref "U16") (pin "50") (pinfunction "TEST_50") (pintype "passive"))
      (node (ref "U16") (pin "52") (pinfunction "GND_52") (pintype "power_in"))
      (node (ref "U16") (pin "53") (pinfunction "PLL_DVSS_53") (pintype "power_in"))
      (node (ref "U16") (pin "56") (pinfunction "PLL_AVSS_56") (pintype "power_in"))
      (node (ref "U16") (pin "57") (pinfunction "GND_57") (pintype "power_in"))
      (node (ref "U16") (pin "8") (pinfunction "GND_8") (pintype "power_in"))
      (node (ref "U17") (pin "12") (pinfunction "GND_12") (pintype "power_in"))
      (node (ref "U17") (pin "13") (pinfunction "VSS_13") (pintype "power_in"))
      (node (ref "U17") (pin "15") (pinfunction "ADDR0_15") (pintype "passive"))
      (node (ref "U17") (pin "16") (pinfunction "ADDR1_16") (pintype "passive"))
      (node (ref "U17") (pin "18") (pinfunction "GND_18") (pintype "power_in"))
      (node (ref "U17") (pin "19") (pinfunction "ADDR2_19") (pintype "passive"))
      (node (ref "U17") (pin "20") (pinfunction "ADDR3_20") (pintype "passive"))
      (node (ref "U17") (pin "22") (pinfunction "GND_22") (pintype "power_in"))
      (node (ref "U17") (pin "26") (pinfunction "GND_26") (pintype "power_in"))
      (node (ref "U17") (pin "28") (pinfunction "ADDR7_28") (pintype "passive"))
      (node (ref "U17") (pin "3") (pinfunction "GND_3") (pintype "power_in"))
      (node (ref "U17") (pin "30") (pinfunction "VSS_30") (pintype "power_in"))
      (node (ref "U17") (pin "31") (pinfunction "GND_31") (pintype "power_in"))
      (node (ref "U17") (pin "35") (pinfunction "GND_35") (pintype "power_in"))
      (node (ref "U17") (pin "41") (pinfunction "GND_41") (pintype "power_in"))
      (node (ref "U17") (pin "42") (pinfunction "VSS_42") (pintype "power_in"))
      (node (ref "U17") (pin "45") (pinfunction "SMODE_45") (pintype "passive"))
      (node (ref "U17") (pin "46") (pinfunction "GND_46") (pintype "power_in"))
      (node (ref "U17") (pin "50") (pinfunction "TEST_50") (pintype "passive"))
      (node (ref "U17") (pin "52") (pinfunction "GND_52") (pintype "power_in"))
      (node (ref "U17") (pin "53") (pinfunction "PLL_DVSS_53") (pintype "power_in"))
      (node (ref "U17") (pin "56") (pinfunction "PLL_AVSS_56") (pintype "power_in"))
      (node (ref "U17") (pin "57") (pinfunction "GND_57") (pintype "power_in"))
      (node (ref "U17") (pin "8") (pinfunction "GND_8") (pintype "power_in"))
      (node (ref "U18") (pin "12") (pinfunction "GND_12") (pintype "power_in"))
      (node (ref "U18") (pin "13") (pinfunction "VSS_13") (pintype "power_in"))
      (node (ref "U18") (pin "15") (pinfunction "ADDR0_15") (pintype "passive"))
      (node (ref "U18") (pin "16") (pinfunction "ADDR1_16") (pintype "passive"))
      (node (ref "U18") (pin "18") (pinfunction "GND_18") (pintype "power_in"))
      (node (ref "U18") (pin "19") (pinfunction "ADDR2_19") (pintype "passive"))
      (node (ref "U18") (pin "22") (pinfunction "GND_22") (pintype "power_in"))
      (node (ref "U18") (pin "26") (pinfunction "GND_26") (pintype "power_in"))
      (node (ref "U18") (pin "28") (pinfunction "ADDR7_28") (pintype "passive"))
      (node (ref "U18") (pin "3") (pinfunction "GND_3") (pintype "power_in"))
      (node (ref "U18") (pin "30") (pinfunction "VSS_30") (pintype "power_in"))
      (node (ref "U18") (pin "31") (pinfunction "GND_31") (pintype "power_in"))
      (node (ref "U18") (pin "35") (pinfunction "GND_35") (pintype "power_in"))
      (node (ref "U18") (pin "41") (pinfunction "GND_41") (pintype "power_in"))
      (node (ref "U18") (pin "42") (pinfunction "VSS_42") (pintype "power_in"))
      (node (ref "U18") (pin "45") (pinfunction "SMODE_45") (pintype "passive"))
      (node (ref "U18") (pin "46") (pinfunction "GND_46") (pintype "power_in"))
      (node (ref "U18") (pin "50") (pinfunction "TEST_50") (pintype "passive"))
      (node (ref "U18") (pin "52") (pinfunction "GND_52") (pintype "power_in"))
      (node (ref "U18") (pin "53") (pinfunction "PLL_DVSS_53") (pintype "power_in"))
      (node (ref "U18") (pin "56") (pinfunction "PLL_AVSS_56") (pintype "power_in"))
      (node (ref "U18") (pin "57") (pinfunction "GND_57") (pintype "power_in"))
      (node (ref "U18") (pin "8") (pinfunction "GND_8") (pintype "power_in"))
    )
    (net (code "48") (name "Net-(U11-PLL_AVDD)") (class "Default")
      (node (ref "C157") (pin "2") (pinfunction "2_2") (pintype "passive"))
      (node (ref "FB9") (pin "1") (pinfunction "1_1") (pintype "passive"))
      (node (ref "U11") (pin "55") (pinfunction "PLL_AVDD_55") (pintype "power_in"))
    )
    (net (code "49") (name "Net-(U12-PLL_AVDD)") (class "Default")
      (node (ref "C159") (pin "2") (pinfunction "2_2") (pintype "passive"))
      (node (ref "FB10") (pin "1") (pinfunction "1_1") (pintype "passive"))
      (node (ref "U12") (pin "55") (pinfunction "PLL_AVDD_55") (pintype "power_in"))
    )
    (net (code "50") (name "Net-(U13-PLL_AVDD)") (class "Default")
      (node (ref "C161") (pin "2") (pinfunction "2_2") (pintype "passive"))
      (node (ref "FB11") (pin "1") (pinfunction "1_1") (pintype "passive"))
      (node (ref "U13") (pin "55") (pinfunction "PLL_AVDD_55") (pintype "power_in"))
    )
    (net (code "51") (name "Net-(U14-PLL_AVDD)") (class "Default")
      (node (ref "C163") (pin "2") (pinfunction "2_2") (pintype "passive"))
      (node (ref "FB12") (pin "1") (pinfunction "1_1") (pintype "passive"))
      (node (ref "U14") (pin "55") (pinfunction "PLL_AVDD_55") (pintype "power_in"))
    )
    (net (code "52") (name "Net-(U15-PLL_AVDD)") (class "Default")
      (node (ref "C221") (pin "2") (pinfunction "2_2") (pintype "passive"))
      (node (ref "FB13") (pin "1") (pinfunction "1_1") (pintype "passive"))
      (node (ref "U15") (pin "55") (pinfunction "PLL_AVDD_55") (pintype "power_in"))
    )
    (net (code "53") (name "Net-(U16-PLL_AVDD)") (class "Default")
      (node (ref "C223") (pin "2") (pinfunction "2_2") (pintype "passive"))
      (node (ref "FB14") (pin "1") (pinfunction "1_1") (pintype "passive"))
      (node (ref "U16") (pin "55") (pinfunction "PLL_AVDD_55") (pintype "power_in"))
    )
    (net (code "54") (name "Net-(U17-PLL_AVDD)") (class "Default")
      (node (ref "C225") (pin "2") (pinfunction "2_2") (pintype "passive"))
      (node (ref "FB15") (pin "1") (pinfunction "1_1") (pintype "passive"))
      (node (ref "U17") (pin "55") (pinfunction "PLL_AVDD_55") (pintype "power_in"))
    )
    (net (code "55") (name "Net-(U18-PLL_AVDD)") (class "Default")
      (node (ref "C227") (pin "2") (pinfunction "2_2") (pintype "passive"))
      (node (ref "FB16") (pin "1") (pinfunction "1_1") (pintype "passive"))
      (node (ref "U18") (pin "55") (pinfunction "PLL_AVDD_55") (pintype "power_in"))
    )
    (net (code "56") (name "VDD2") (class "Default")
      (node (ref "C152") (pin "1") (pinfunction "1_1") (pintype "passive"))
      (node (ref "C153") (pin "1") (pinfunction "1_1") (pintype "passive"))
      (node (ref "C154") (pin "2") (pinfunction "2_2") (pintype "passive"))
      (node (ref "C155") (pin "2") (pinfunction "2_2") (pintype "passive"))
      (node (ref "C176") (pin "2") (pinfunction "2_2") (pintype "passive"))
      (node (ref "C177") (pin "2") (pinfunction "2_2") (pintype "passive"))
      (node (ref "C178") (pin "2") (pinfunction "2_2") (pintype "passive"))
      (node (ref "C179") (pin "2") (pinfunction "2_2") (pintype "passive"))
      (node (ref "C180") (pin "2") (pinfunction "2_2") (pintype "passive"))
      (node (ref "C181") (pin "2") (pinfunction "2_2") (pintype "passive"))
      (node (ref "C182") (pin "2") (pinfunction "2_2") (pintype "passive"))
      (node (ref "C183") (pin "2") (pinfunction "2_2") (pintype "passive"))
      (node (ref "C184") (pin "2") (pinfunction "2_2") (pintype "passive"))
      (node (ref "C185") (pin "2") (pinfunction "2_2") (pintype "passive"))
      (node (ref "C186") (pin "2") (pinfunction "2_2") (pintype "passive"))
      (node (ref "C187") (pin "2") (pinfunction "2_2") (pintype "passive"))
      (node (ref "C188") (pin "2") (pinfunction "2_2") (pintype "passive"))
      (node (ref "C189") (pin "2") (pinfunction "2_2") (pintype "passive"))
      (node (ref "C190") (pin "2") (pinfunction "2_2") (pintype "passive"))
      (node (ref "C191") (pin "2") (pinfunction "2_2") (pintype "passive"))
      (node (ref "C192") (pin "2") (pinfunction "2_2") (pintype "passive"))
      (node (ref "C193") (pin "2") (pinfunction "2_2") (pintype "passive"))
      (node (ref "C194") (pin "2") (pinfunction "2_2") (pintype "passive"))
      (node (ref "C195") (pin "2") (pinfunction "2_2") (pintype "passive"))
      (node (ref "C196") (pin "2") (pinfunction "2_2") (pintype "passive"))
      (node (ref "C197") (pin "2") (pinfunction "2_2") (pintype "passive"))
      (node (ref "C198") (pin "2") (pinfunction "2_2") (pintype "passive"))
      (node (ref "C199") (pin "2") (pinfunction "2_2") (pintype "passive"))
      (node (ref "C200") (pin "2") (pinfunction "2_2") (pintype "passive"))
      (node (ref "C201") (pin "2") (pinfunction "2_2") (pintype "passive"))
      (node (ref "C202") (pin "2") (pinfunction "2_2") (pintype "passive"))
      (node (ref "C203") (pin "2") (pinfunction "2_2") (pintype "passive"))
      (node (ref "C204") (pin "2") (pinfunction "2_2") (pintype "passive"))
      (node (ref "C205") (pin "2") (pinfunction "2_2") (pintype "passive"))
      (node (ref "C206") (pin "2") (pinfunction "2_2") (pintype "passive"))
      (node (ref "C207") (pin "2") (pinfunction "2_2") (pintype "passive"))
      (node (ref "C208") (pin "2") (pinfunction "2_2") (pintype "passive"))
      (node (ref "C209") (pin "2") (pinfunction "2_2") (pintype "passive"))
      (node (ref "C210") (pin "2") (pinfunction "2_2") (pintype "passive"))
      (node (ref "C211") (pin "2") (pinfunction "2_2") (pintype "passive"))
      (node (ref "C212") (pin "2") (pinfunction "2_2") (pintype "passive"))
      (node (ref "C213") (pin "2") (pinfunction "2_2") (pintype "passive"))
      (node (ref "C214") (pin "2") (pinfunction "2_2") (pintype "passive"))
      (node (ref "C215") (pin "2") (pinfunction "2_2") (pintype "passive"))
      (node (ref "C216") (pin "2") (pinfunction "2_2") (pintype "passive"))
      (node (ref "C217") (pin "2") (pinfunction "2_2") (pintype "passive"))
      (node (ref "C218") (pin "2") (pinfunction "2_2") (pintype "passive"))
      (node (ref "C219") (pin "2") (pinfunction "2_2") (pintype "passive"))
      (node (ref "C240") (pin "2") (pinfunction "2_2") (pintype "passive"))
      (node (ref "C241") (pin "2") (pinfunction "2_2") (pintype "passive"))
      (node (ref "C242") (pin "2") (pinfunction "2_2") (pintype "passive"))
      (node (ref "C243") (pin "2") (pinfunction "2_2") (pintype "passive"))
      (node (ref "C244") (pin "2") (pinfunction "2_2") (pintype "passive"))
      (node (ref "C245") (pin "2") (pinfunction "2_2") (pintype "passive"))
      (node (ref "C246") (pin "2") (pinfunction "2_2") (pintype "passive"))
      (node (ref "C247") (pin "2") (pinfunction "2_2") (pintype "passive"))
      (node (ref "C248") (pin "2") (pinfunction "2_2") (pintype "passive"))
      (node (ref "C249") (pin "2") (pinfunction "2_2") (pintype "passive"))
      (node (ref "C250") (pin "2") (pinfunction "2_2") (pintype "passive"))
      (node (ref "C251") (pin "2") (pinfunction "2_2") (pintype "passive"))
      (node (ref "C252") (pin "2") (pinfunction "2_2") (pintype "passive"))
      (node (ref "C253") (pin "2") (pinfunction "2_2") (pintype "passive"))
      (node (ref "C254") (pin "2") (pinfunction "2_2") (pintype "passive"))
      (node (ref "C255") (pin "2") (pinfunction "2_2") (pintype "passive"))
      (node (ref "C256") (pin "2") (pinfunction "2_2") (pintype "passive"))
      (node (ref "C257") (pin "2") (pinfunction "2_2") (pintype "passive"))
      (node (ref "C258") (pin "2") (pinfunction "2_2") (pintype "passive"))
      (node (ref "C259") (pin "2") (pinfunction "2_2") (pintype "passive"))
      (node (ref "C260") (pin "2") (pinfunction "2_2") (pintype "passive"))
      (node (ref "C261") (pin "2") (pinfunction "2_2") (pintype "passive"))
      (node (ref "C262") (pin "2") (pinfunction "2_2") (pintype "passive"))
      (node (ref "C263") (pin "2") (pinfunction "2_2") (pintype "passive"))
      (node (ref "C264") (pin "2") (pinfunction "2_2") (pintype "passive"))
      (node (ref "C265") (pin "2") (pinfunction "2_2") (pintype "passive"))
      (node (ref "C266") (pin "2") (pinfunction "2_2") (pintype "passive"))
      (node (ref "C267") (pin "2") (pinfunction "2_2") (pintype "passive"))
      (node (ref "C268") (pin "2") (pinfunction "2_2") (pintype "passive"))
      (node (ref "C269") (pin "2") (pinfunction "2_2") (pintype "passive"))
      (node (ref "C270") (pin "2") (pinfunction "2_2") (pintype "passive"))
      (node (ref "C271") (pin "2") (pinfunction "2_2") (pintype "passive"))
      (node (ref "C272") (pin "2") (pinfunction "2_2") (pintype "passive"))
      (node (ref "C273") (pin "2") (pinfunction "2_2") (pintype "passive"))
      (node (ref "C274") (pin "2") (pinfunction "2_2") (pintype "passive"))
      (node (ref "C275") (pin "2") (pinfunction "2_2") (pintype "passive"))
      (node (ref "C276") (pin "2") (pinfunction "2_2") (pintype "passive"))
      (node (ref "C277") (pin "2") (pinfunction "2_2") (pintype "passive"))
      (node (ref "C278") (pin "2") (pinfunction "2_2") (pintype "passive"))
      (node (ref "C279") (pin "2") (pinfunction "2_2") (pintype "passive"))
      (node (ref "C280") (pin "2") (pinfunction "2_2") (pintype "passive"))
      (node (ref "C281") (pin "2") (pinfunction "2_2") (pintype "passive"))
      (node (ref "C282") (pin "2") (pinfunction "2_2") (pintype "passive"))
      (node (ref "C283") (pin "2") (pinfunction "2_2") (pintype "passive"))
      (node (ref "U11") (pin "11") (pinfunction "VDD_11") (pintype "power_in"))
      (node (ref "U11") (pin "17") (pinfunction "VDD_17") (pintype "power_in"))
      (node (ref "U11") (pin "21") (pinfunction "VDD_21") (pintype "power_in"))
      (node (ref "U11") (pin "25") (pinfunction "VDD_25") (pintype "power_in"))
      (node (ref "U11") (pin "32") (pinfunction "VDD_32") (pintype "power_in"))
      (node (ref "U11") (pin "36") (pinfunction "VDD_36") (pintype "power_in"))
      (node (ref "U11") (pin "4") (pinfunction "VDD_4") (pintype "power_in"))
      (node (ref "U11") (pin "40") (pinfunction "VDD_40") (pintype "power_in"))
      (node (ref "U11") (pin "47") (pinfunction "VDD_47") (pintype "power_in"))
      (node (ref "U11") (pin "51") (pinfunction "VDD_51") (pintype "power_in"))
      (node (ref "U11") (pin "7") (pinfunction "VDD_7") (pintype "power_in"))
      (node (ref "U12") (pin "11") (pinfunction "VDD_11") (pintype "power_in"))
      (node (ref "U12") (pin "17") (pinfunction "VDD_17") (pintype "power_in"))
      (node (ref "U12") (pin "21") (pinfunction "VDD_21") (pintype "power_in"))
      (node (ref "U12") (pin "25") (pinfunction "VDD_25") (pintype "power_in"))
      (node (ref "U12") (pin "32") (pinfunction "VDD_32") (pintype "power_in"))
      (node (ref "U12") (pin "36") (pinfunction "VDD_36") (pintype "power_in"))
      (node (ref "U12") (pin "4") (pinfunction "VDD_4") (pintype "power_in"))
      (node (ref "U12") (pin "40") (pinfunction "VDD_40") (pintype "power_in"))
      (node (ref "U12") (pin "47") (pinfunction "VDD_47") (pintype "power_in"))
      (node (ref "U12") (pin "51") (pinfunction "VDD_51") (pintype "power_in"))
      (node (ref "U12") (pin "7") (pinfunction "VDD_7") (pintype "power_in"))
      (node (ref "U13") (pin "11") (pinfunction "VDD_11") (pintype "power_in"))
      (node (ref "U13") (pin "17") (pinfunction "VDD_17") (pintype "power_in"))
      (node (ref "U13") (pin "21") (pinfunction "VDD_21") (pintype "power_in"))
      (node (ref "U13") (pin "25") (pinfunction "VDD_25") (pintype "power_in"))
      (node (ref "U13") (pin "32") (pinfunction "VDD_32") (pintype "power_in"))
      (node (ref "U13") (pin "36") (pinfunction "VDD_36") (pintype "power_in"))
      (node (ref "U13") (pin "4") (pinfunction "VDD_4") (pintype "power_in"))
      (node (ref "U13") (pin "40") (pinfunction "VDD_40") (pintype "power_in"))
      (node (ref "U13") (pin "47") (pinfunction "VDD_47") (pintype "power_in"))
      (node (ref "U13") (pin "51") (pinfunction "VDD_51") (pintype "power_in"))
      (node (ref "U13") (pin "7") (pinfunction "VDD_7") (pintype "power_in"))
      (node (ref "U14") (pin "11") (pinfunction "VDD_11") (pintype "power_in"))
      (node (ref "U14") (pin "17") (pinfunction "VDD_17") (pintype "power_in"))
      (node (ref "U14") (pin "21") (pinfunction "VDD_21") (pintype "power_in"))
      (node (ref "U14") (pin "25") (pinfunction "VDD_25") (pintype "power_in"))
      (node (ref "U14") (pin "32") (pinfunction "VDD_32") (pintype "power_in"))
      (node (ref "U14") (pin "36") (pinfunction "VDD_36") (pintype "power_in"))
      (node (ref "U14") (pin "4") (pinfunction "VDD_4") (pintype "power_in"))
      (node (ref "U14") (pin "40") (pinfunction "VDD_40") (pintype "power_in"))
      (node (ref "U14") (pin "47") (pinfunction "VDD_47") (pintype "power_in"))
      (node (ref "U14") (pin "51") (pinfunction "VDD_51") (pintype "power_in"))
      (node (ref "U14") (pin "7") (pinfunction "VDD_7") (pintype "power_in"))
      (node (ref "U15") (pin "11") (pinfunction "VDD_11") (pintype "power_in"))
      (node (ref "U15") (pin "17") (pinfunction "VDD_17") (pintype "power_in"))
      (node (ref "U15") (pin "21") (pinfunction "VDD_21") (pintype "power_in"))
      (node (ref "U15") (pin "25") (pinfunction "VDD_25") (pintype "power_in"))
      (node (ref "U15") (pin "32") (pinfunction "VDD_32") (pintype "power_in"))
      (node (ref "U15") (pin "36") (pinfunction "VDD_36") (pintype "power_in"))
      (node (ref "U15") (pin "4") (pinfunction "VDD_4") (pintype "power_in"))
      (node (ref "U15") (pin "40") (pinfunction "VDD_40") (pintype "power_in"))
      (node (ref "U15") (pin "47") (pinfunction "VDD_47") (pintype "power_in"))
      (node (ref "U15") (pin "51") (pinfunction "VDD_51") (pintype "power_in"))
      (node (ref "U15") (pin "7") (pinfunction "VDD_7") (pintype "power_in"))
      (node (ref "U16") (pin "11") (pinfunction "VDD_11") (pintype "power_in"))
      (node (ref "U16") (pin "17") (pinfunction "VDD_17") (pintype "power_in"))
      (node (ref "U16") (pin "21") (pinfunction "VDD_21") (pintype "power_in"))
      (node (ref "U16") (pin "25") (pinfunction "VDD_25") (pintype "power_in"))
      (node (ref "U16") (pin "32") (pinfunction "VDD_32") (pintype "power_in"))
      (node (ref "U16") (pin "36") (pinfunction "VDD_36") (pintype "power_in"))
      (node (ref "U16") (pin "4") (pinfunction "VDD_4") (pintype "power_in"))
      (node (ref "U16") (pin "40") (pinfunction "VDD_40") (pintype "power_in"))
      (node (ref "U16") (pin "47") (pinfunction "VDD_47") (pintype "power_in"))
      (node (ref "U16") (pin "51") (pinfunction "VDD_51") (pintype "power_in"))
      (node (ref "U16") (pin "7") (pinfunction "VDD_7") (pintype "power_in"))
      (node (ref "U17") (pin "11") (pinfunction "VDD_11") (pintype "power_in"))
      (node (ref "U17") (pin "17") (pinfunction "VDD_17") (pintype "power_in"))
      (node (ref "U17") (pin "21") (pinfunction "VDD_21") (pintype "power_in"))
      (node (ref "U17") (pin "25") (pinfunction "VDD_25") (pintype "power_in"))
      (node (ref "U17") (pin "32") (pinfunction "VDD_32") (pintype "power_in"))
      (node (ref "U17") (pin "36") (pinfunction "VDD_36") (pintype "power_in"))
      (node (ref "U17") (pin "4") (pinfunction "VDD_4") (pintype "power_in"))
      (node (ref "U17") (pin "40") (pinfunction "VDD_40") (pintype "power_in"))
      (node (ref "U17") (pin "47") (pinfunction "VDD_47") (pintype "power_in"))
      (node (ref "U17") (pin "51") (pinfunction "VDD_51") (pintype "power_in"))
      (node (ref "U17") (pin "7") (pinfunction "VDD_7") (pintype "power_in"))
      (node (ref "U18") (pin "11") (pinfunction "VDD_11") (pintype "power_in"))
      (node (ref "U18") (pin "17") (pinfunction "VDD_17") (pintype "power_in"))
      (node (ref "U18") (pin "21") (pinfunction "VDD_21") (pintype "power_in"))
      (node (ref "U18") (pin "25") (pinfunction "VDD_25") (pintype "power_in"))
      (node (ref "U18") (pin "32") (pinfunction "VDD_32") (pintype "power_in"))
      (node (ref "U18") (pin "36") (pinfunction "VDD_36") (pintype "power_in"))
      (node (ref "U18") (pin "4") (pinfunction "VDD_4") (pintype "power_in"))
      (node (ref "U18") (pin "40") (pinfunction "VDD_40") (pintype "power_in"))
      (node (ref "U18") (pin "47") (pinfunction "VDD_47") (pintype "power_in"))
      (node (ref "U18") (pin "51") (pinfunction "VDD_51") (pintype "power_in"))
      (node (ref "U18") (pin "7") (pinfunction "VDD_7") (pintype "power_in"))
    )
    (net (code "57") (name "VPLL2") (class "Default")
      (node (ref "C156") (pin "1") (pinfunction "1_1") (pintype "passive"))
      (node (ref "C158") (pin "1") (pinfunction "1_1") (pintype "passive"))
      (node (ref "C160") (pin "1") (pinfunction "1_1") (pintype "passive"))
      (node (ref "C162") (pin "1") (pinfunction "1_1") (pintype "passive"))
      (node (ref "C220") (pin "1") (pinfunction "1_1") (pintype "passive"))
      (node (ref "C222") (pin "1") (pinfunction "1_1") (pintype "passive"))
      (node (ref "C224") (pin "1") (pinfunction "1_1") (pintype "passive"))
      (node (ref "C226") (pin "1") (pinfunction "1_1") (pintype "passive"))
      (node (ref "FB10") (pin "2") (pinfunction "2_2") (pintype "passive"))
      (node (ref "FB11") (pin "2") (pinfunction "2_2") (pintype "passive"))
      (node (ref "FB12") (pin "2") (pinfunction "2_2") (pintype "passive"))
      (node (ref "FB13") (pin "2") (pinfunction "2_2") (pintype "passive"))
      (node (ref "FB14") (pin "2") (pinfunction "2_2") (pintype "passive"))
      (node (ref "FB15") (pin "2") (pinfunction "2_2") (pintype "passive"))
      (node (ref "FB16") (pin "2") (pinfunction "2_2") (pintype "passive"))
      (node (ref "FB9") (pin "2") (pinfunction "2_2") (pintype "passive"))
      (node (ref "U11") (pin "54") (pinfunction "PLL_DVDD_54") (pintype "power_in"))
      (node (ref "U12") (pin "54") (pinfunction "PLL_DVDD_54") (pintype "power_in"))
      (node (ref "U13") (pin "54") (pinfunction "PLL_DVDD_54") (pintype "power_in"))
      (node (ref "U14") (pin "54") (pinfunction "PLL_DVDD_54") (pintype "power_in"))
      (node (ref "U15") (pin "54") (pinfunction "PLL_DVDD_54") (pintype "power_in"))
      (node (ref "U16") (pin "54") (pinfunction "PLL_DVDD_54") (pintype "power_in"))
      (node (ref "U17") (pin "54") (pinfunction "PLL_DVDD_54") (pintype "power_in"))
      (node (ref "U18") (pin "54") (pinfunction "PLL_DVDD_54") (pintype "power_in"))
    )
    (net (code "58") (name "unconnected-(U11-CMODE-Pad44)") (class "Default")
      (node (ref "U11") (pin "44") (pinfunction "CMODE_44") (pintype "passive+no_connect"))
    )
    (net (code "59") (name "unconnected-(U11-RF-Pad49)") (class "Default")
      (node (ref "U11") (pin "49") (pinfunction "RF_49") (pintype "output+no_connect"))
    )
    (net (code "60") (name "unconnected-(U11-TF-Pad48)") (class "Default")
      (node (ref "U11") (pin "48") (pinfunction "TF_48") (pintype "output+no_connect"))
    )
    (net (code "61") (name "unconnected-(U11-XOUT-Pad2)") (class "Default")
      (node (ref "U11") (pin "2") (pinfunction "XOUT_2") (pintype "output+no_connect"))
    )
    (net (code "62") (name "unconnected-(U12-CMODE-Pad44)") (class "Default")
      (node (ref "U12") (pin "44") (pinfunction "CMODE_44") (pintype "passive+no_connect"))
    )
    (net (code "63") (name "unconnected-(U12-RF-Pad49)") (class "Default")
      (node (ref "U12") (pin "49") (pinfunction "RF_49") (pintype "output+no_connect"))
    )
    (net (code "64") (name "unconnected-(U12-TF-Pad48)") (class "Default")
      (node (ref "U12") (pin "48") (pinfunction "TF_48") (pintype "output+no_connect"))
    )
    (net (code "65") (name "unconnected-(U12-XOUT-Pad2)") (class "Default")
      (node (ref "U12") (pin "2") (pinfunction "XOUT_2") (pintype "output+no_connect"))
    )
    (net (code "66") (name "unconnected-(U13-CMODE-Pad44)") (class "Default")
      (node (ref "U13") (pin "44") (pinfunction "CMODE_44") (pintype "passive+no_connect"))
    )
    (net (code "67") (name "unconnected-(U13-RF-Pad49)") (class "Default")
      (node (ref "U13") (pin "49") (pinfunction "RF_49") (pintype "output+no_connect"))
    )
    (net (code "68") (name "unconnected-(U13-TF-Pad48)") (class "Default")
      (node (ref "U13") (pin "48") (pinfunction "TF_48") (pintype "output+no_connect"))
    )
    (net (code "69") (name "unconnected-(U13-XOUT-Pad2)") (class "Default")
      (node (ref "U13") (pin "2") (pinfunction "XOUT_2") (pintype "output+no_connect"))
    )
    (net (code "70") (name "unconnected-(U14-CMODE-Pad44)") (class "Default")
      (node (ref "U14") (pin "44") (pinfunction "CMODE_44") (pintype "passive+no_connect"))
    )
    (net (code "71") (name "unconnected-(U14-RF-Pad49)") (class "Default")
      (node (ref "U14") (pin "49") (pinfunction "RF_49") (pintype "output+no_connect"))
    )
    (net (code "72") (name "unconnected-(U14-TF-Pad48)") (class "Default")
      (node (ref "U14") (pin "48") (pinfunction "TF_48") (pintype "output+no_connect"))
    )
    (net (code "73") (name "unconnected-(U14-XOUT-Pad2)") (class "Default")
      (node (ref "U14") (pin "2") (pinfunction "XOUT_2") (pintype "output+no_connect"))
    )
    (net (code "74") (name "unconnected-(U15-CMODE-Pad44)") (class "Default")
      (node (ref "U15") (pin "44") (pinfunction "CMODE_44") (pintype "passive+no_connect"))
    )
    (net (code "75") (name "unconnected-(U15-RF-Pad49)") (class "Default")
      (node (ref "U15") (pin "49") (pinfunction "RF_49") (pintype "output+no_connect"))
    )
    (net (code "76") (name "unconnected-(U15-TF-Pad48)") (class "Default")
      (node (ref "U15") (pin "48") (pinfunction "TF_48") (pintype "output+no_connect"))
    )
    (net (code "77") (name "unconnected-(U15-XOUT-Pad2)") (class "Default")
      (node (ref "U15") (pin "2") (pinfunction "XOUT_2") (pintype "output+no_connect"))
    )
    (net (code "78") (name "unconnected-(U16-CMODE-Pad44)") (class "Default")
      (node (ref "U16") (pin "44") (pinfunction "CMODE_44") (pintype "passive+no_connect"))
    )
    (net (code "79") (name "unconnected-(U16-RF-Pad49)") (class "Default")
      (node (ref "U16") (pin "49") (pinfunction "RF_49") (pintype "output+no_connect"))
    )
    (net (code "80") (name "unconnected-(U16-TF-Pad48)") (class "Default")
      (node (ref "U16") (pin "48") (pinfunction "TF_48") (pintype "output+no_connect"))
    )
    (net (code "81") (name "unconnected-(U16-XOUT-Pad2)") (class "Default")
      (node (ref "U16") (pin "2") (pinfunction "XOUT_2") (pintype "output+no_connect"))
    )
    (net (code "82") (name "unconnected-(U17-CMODE-Pad44)") (class "Default")
      (node (ref "U17") (pin "44") (pinfunction "CMODE_44") (pintype "passive+no_connect"))
    )
    (net (code "83") (name "unconnected-(U17-RF-Pad49)") (class "Default")
      (node (ref "U17") (pin "49") (pinfunction "RF_49") (pintype "output+no_connect"))
    )
    (net (code "84") (name "unconnected-(U17-TF-Pad48)") (class "Default")
      (node (ref "U17") (pin "48") (pinfunction "TF_48") (pintype "output+no_connect"))
    )
    (net (code "85") (name "unconnected-(U17-XOUT-Pad2)") (class "Default")
      (node (ref "U17") (pin "2") (pinfunction "XOUT_2") (pintype "output+no_connect"))
    )
    (net (code "86") (name "unconnected-(U18-CMODE-Pad44)") (class "Default")
      (node (ref "U18") (pin "44") (pinfunction "CMODE_44") (pintype "passive+no_connect"))
    )
    (net (code "87") (name "unconnected-(U18-RF-Pad49)") (class "Default")
      (node (ref "U18") (pin "49") (pinfunction "RF_49") (pintype "output+no_connect"))
    )
    (net (code "88") (name "unconnected-(U18-TF-Pad48)") (class "Default")
      (node (ref "U18") (pin "48") (pinfunction "TF_48") (pintype "output+no_connect"))
    )
    (net (code "89") (name "unconnected-(U18-XOUT-Pad2)") (class "Default")
      (node (ref "U18") (pin "2") (pinfunction "XOUT_2") (pintype "output+no_connect"))
    )
  )
)
